# M8310F.net
KiCad netlist of a schematic drawn in EAGLE
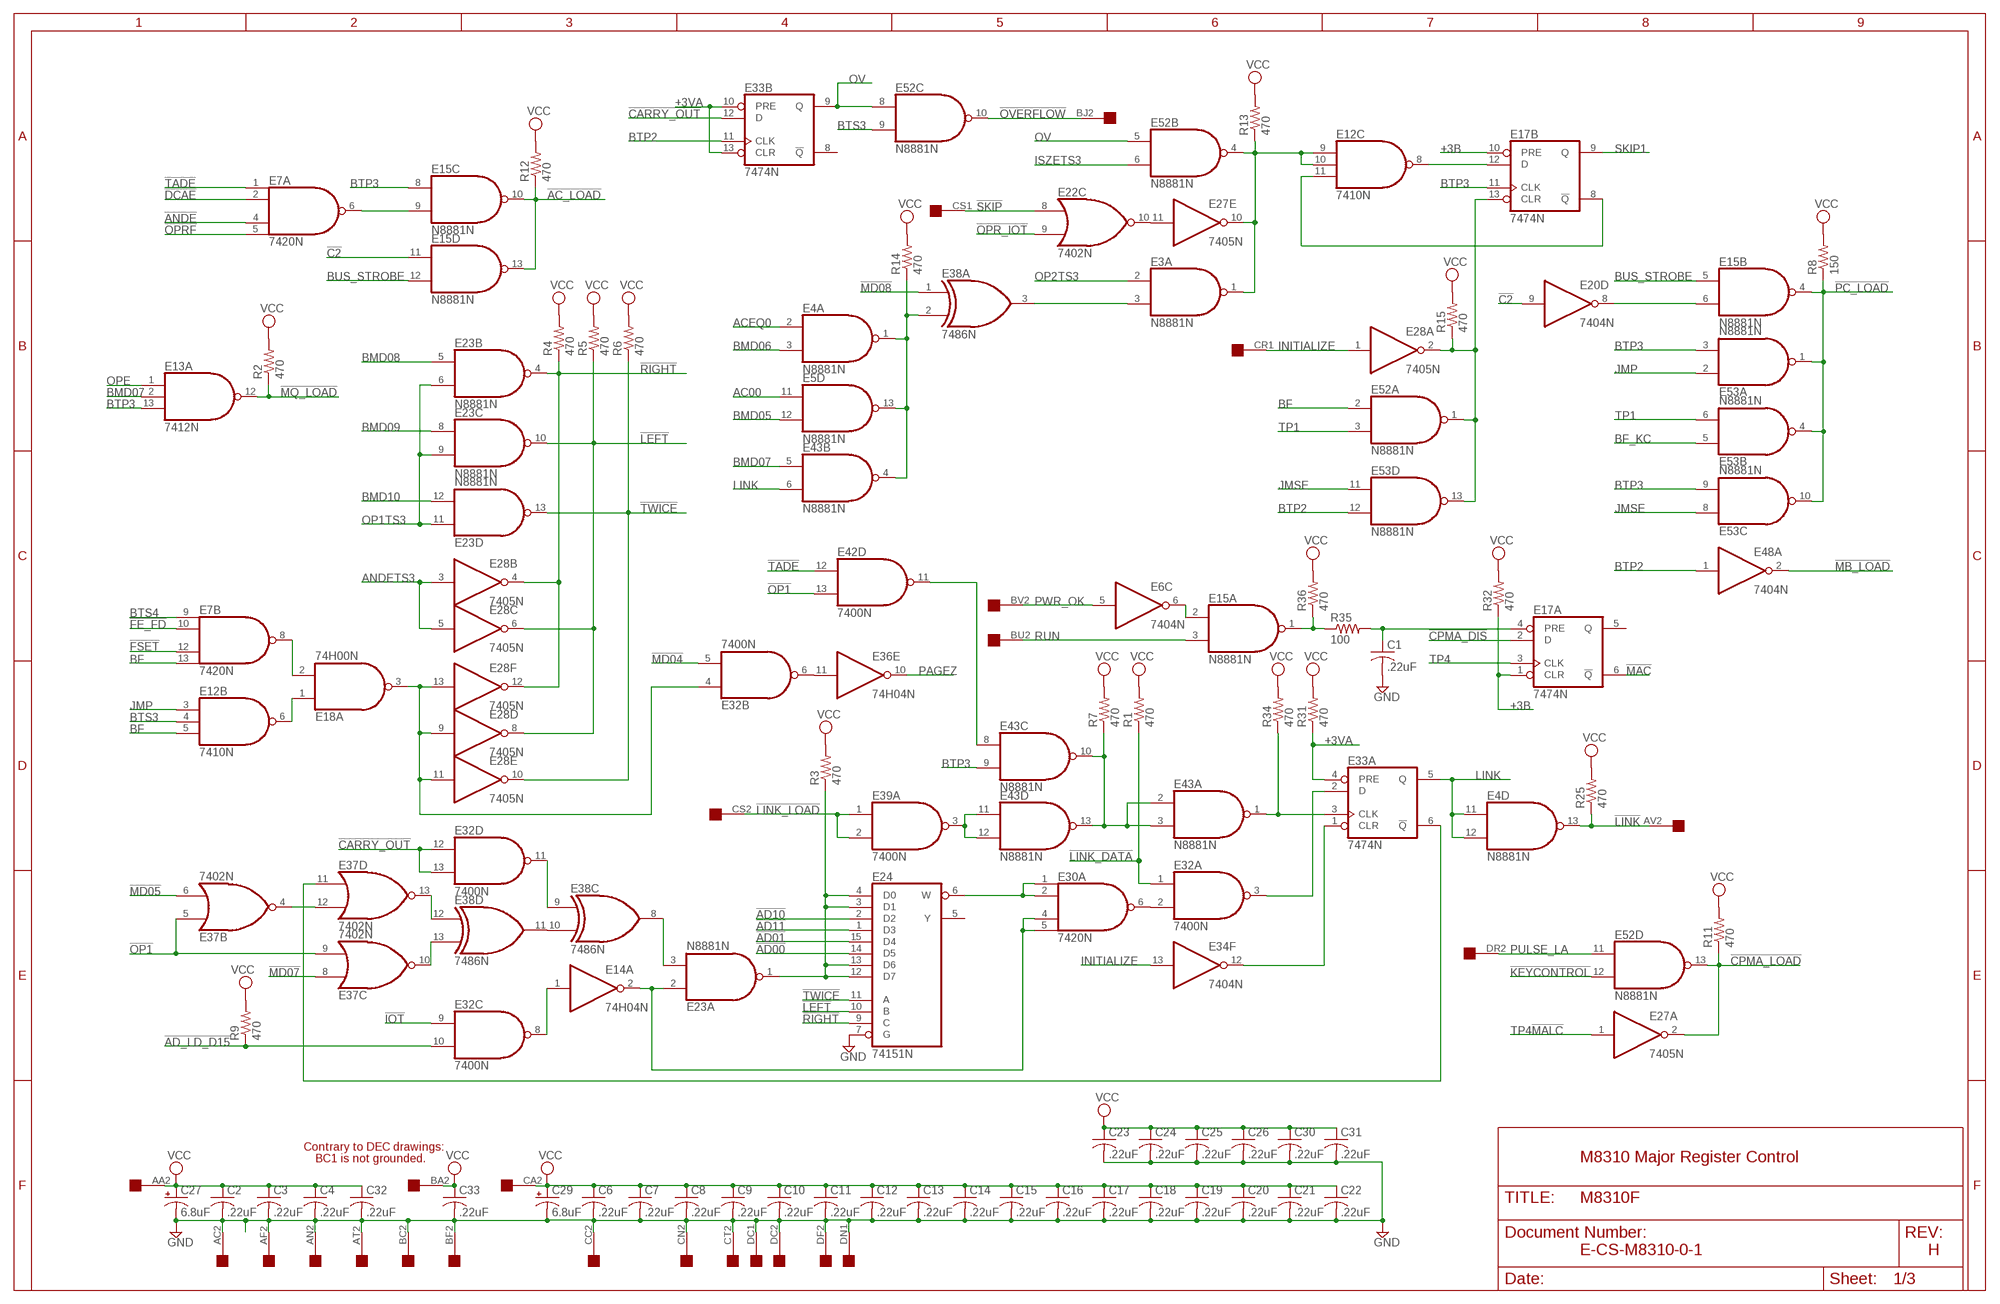
[diagram p0: schematic, sheet 1]
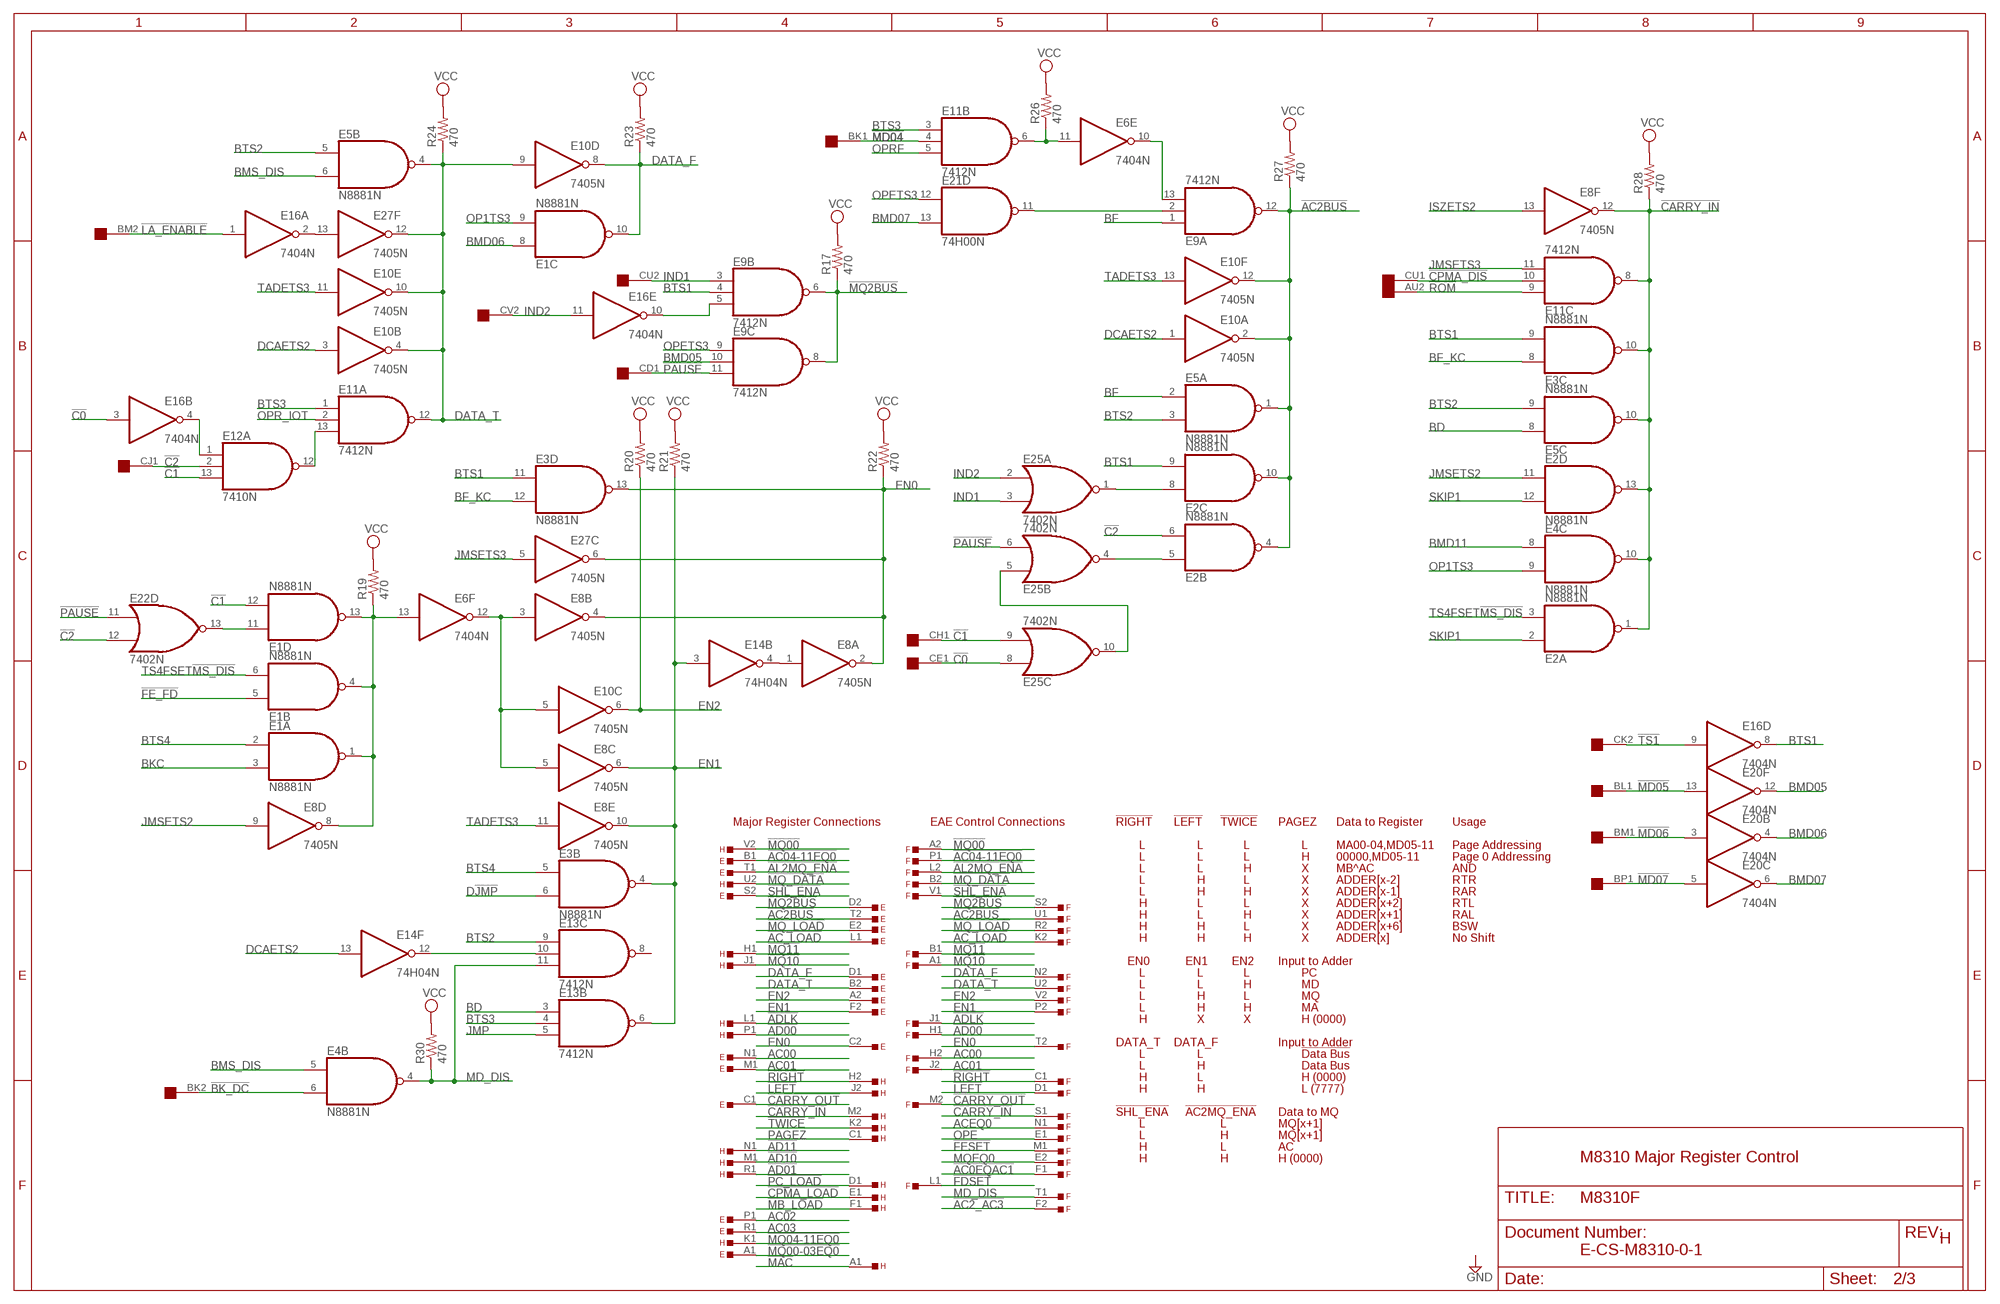
[diagram p1: schematic, sheet 2]
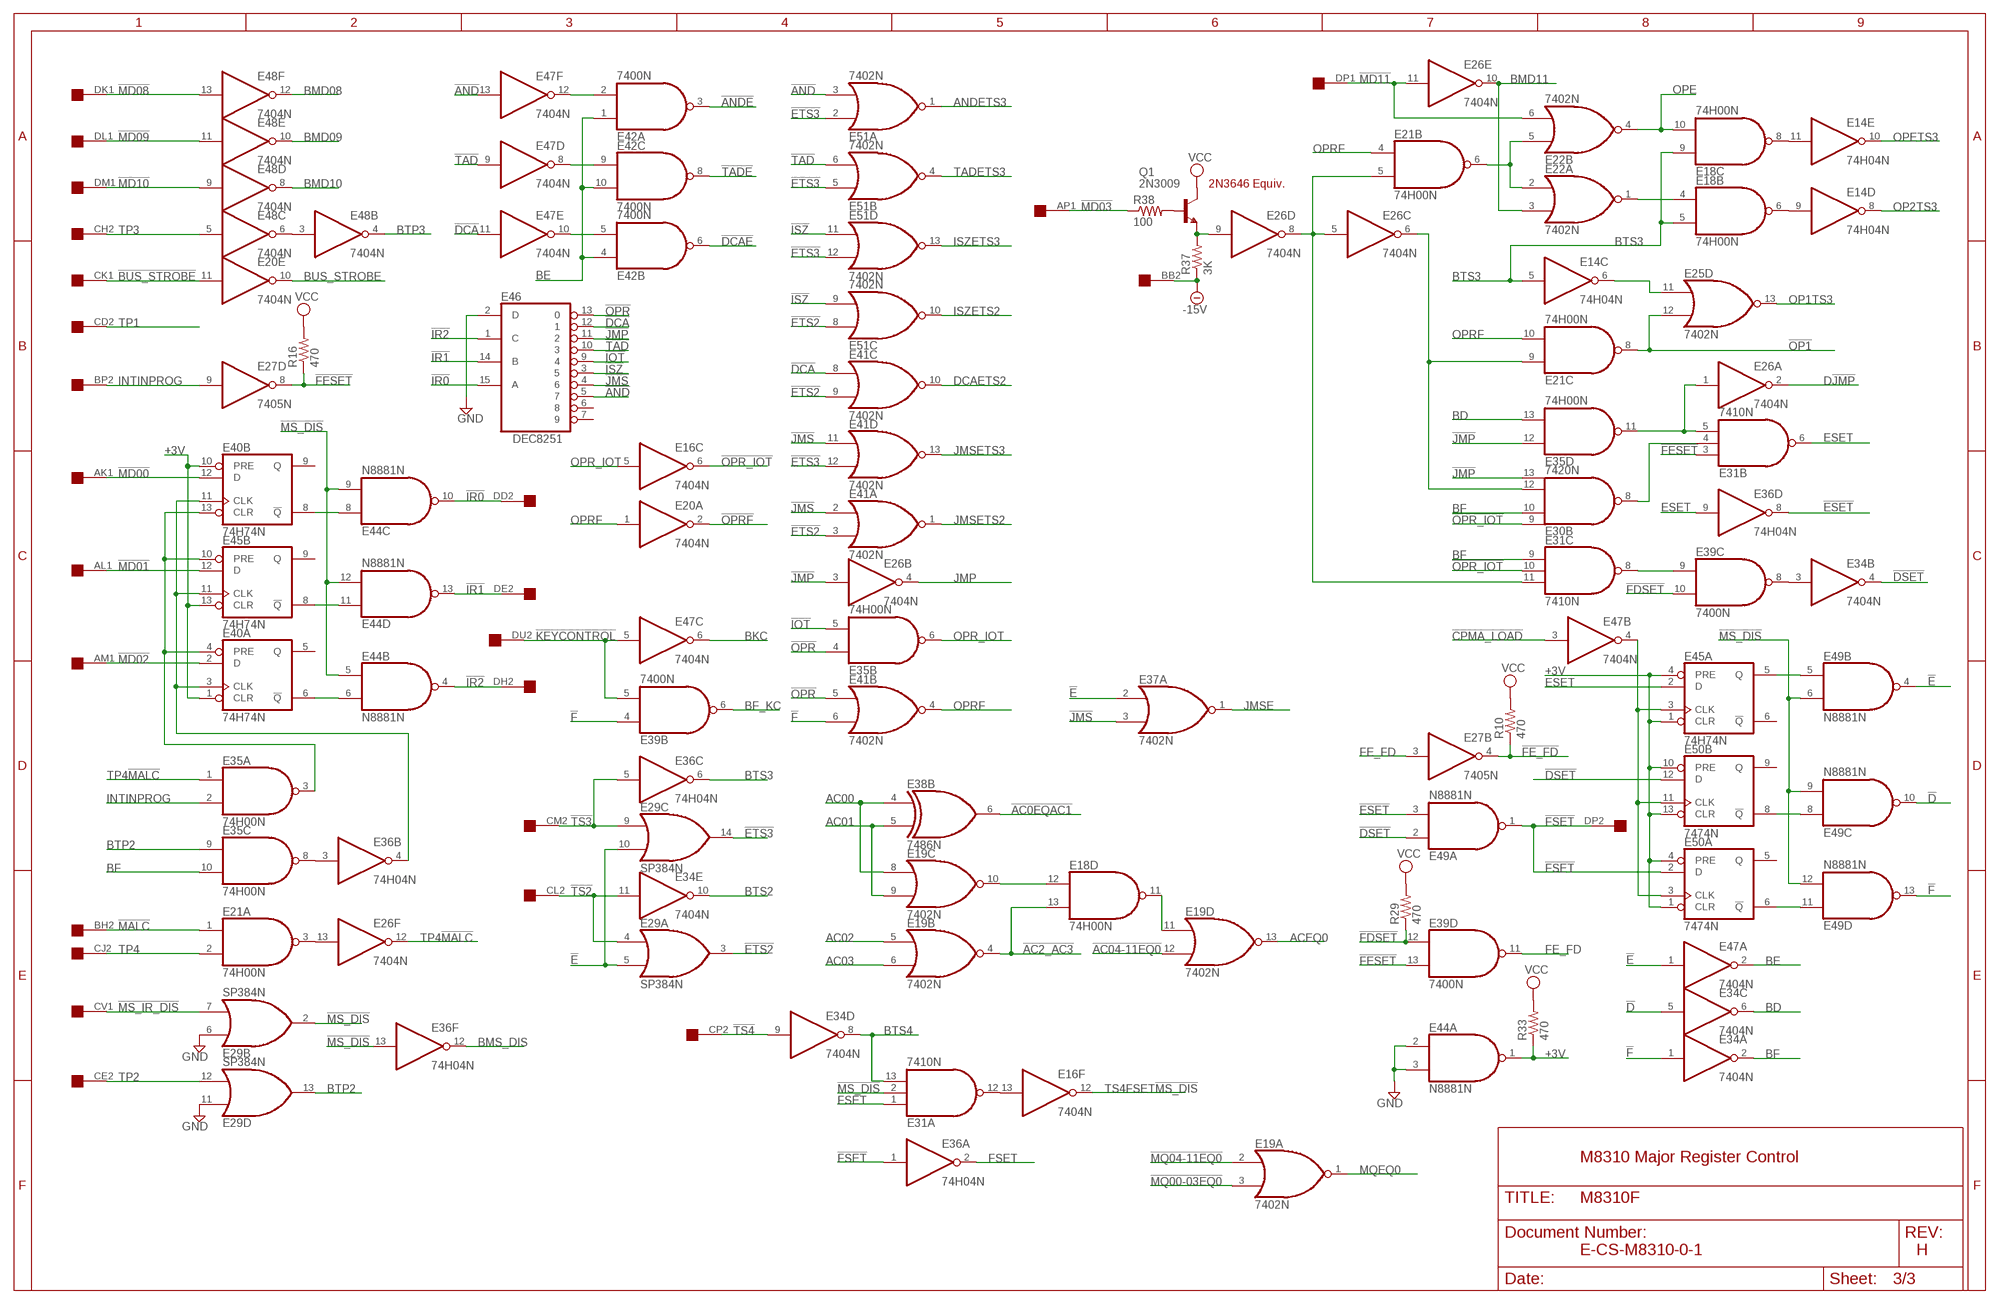
[diagram p2: schematic, sheet 3]

(export (version "E")
  (design (tool "Eeschema 10.0.6"))
  (components
    (comp (ref "C1")
      (value ".22uF")
      (footprint "eagle-import:C063-025X075")
      (libsource (lib "eagle-import") (part "C-US"))
    )
    (comp (ref "C2")
      (value ".22uF")
      (footprint "eagle-import:C063-025X075")
      (libsource (lib "eagle-import") (part "C-US"))
    )
    (comp (ref "C3")
      (value ".22uF")
      (footprint "eagle-import:C063-025X075")
      (libsource (lib "eagle-import") (part "C-US"))
    )
    (comp (ref "C4")
      (value ".22uF")
      (footprint "eagle-import:C063-025X075")
      (libsource (lib "eagle-import") (part "C-US"))
    )
    (comp (ref "C6")
      (value ".22uF")
      (footprint "eagle-import:C063-025X075")
      (libsource (lib "eagle-import") (part "C-US"))
    )
    (comp (ref "C7")
      (value ".22uF")
      (footprint "eagle-import:C063-025X075")
      (libsource (lib "eagle-import") (part "C-US"))
    )
    (comp (ref "C8")
      (value ".22uF")
      (footprint "eagle-import:C063-025X075")
      (libsource (lib "eagle-import") (part "C-US"))
    )
    (comp (ref "C9")
      (value ".22uF")
      (footprint "eagle-import:C063-025X075")
      (libsource (lib "eagle-import") (part "C-US"))
    )
    (comp (ref "C10")
      (value ".22uF")
      (footprint "eagle-import:C063-025X075")
      (libsource (lib "eagle-import") (part "C-US"))
    )
    (comp (ref "C11")
      (value ".22uF")
      (footprint "eagle-import:C063-025X075")
      (libsource (lib "eagle-import") (part "C-US"))
    )
    (comp (ref "C12")
      (value ".22uF")
      (footprint "eagle-import:C063-025X075")
      (libsource (lib "eagle-import") (part "C-US"))
    )
    (comp (ref "C13")
      (value ".22uF")
      (footprint "eagle-import:C063-025X075")
      (libsource (lib "eagle-import") (part "C-US"))
    )
    (comp (ref "C14")
      (value ".22uF")
      (footprint "eagle-import:C063-025X075")
      (libsource (lib "eagle-import") (part "C-US"))
    )
    (comp (ref "C15")
      (value ".22uF")
      (footprint "eagle-import:C063-025X075")
      (libsource (lib "eagle-import") (part "C-US"))
    )
    (comp (ref "C16")
      (value ".22uF")
      (footprint "eagle-import:C063-025X075")
      (libsource (lib "eagle-import") (part "C-US"))
    )
    (comp (ref "C17")
      (value ".22uF")
      (footprint "eagle-import:C063-025X075")
      (libsource (lib "eagle-import") (part "C-US"))
    )
    (comp (ref "C18")
      (value ".22uF")
      (footprint "eagle-import:C063-025X075")
      (libsource (lib "eagle-import") (part "C-US"))
    )
    (comp (ref "C19")
      (value ".22uF")
      (footprint "eagle-import:C063-025X075")
      (libsource (lib "eagle-import") (part "C-US"))
    )
    (comp (ref "C20")
      (value ".22uF")
      (footprint "eagle-import:C063-025X075")
      (libsource (lib "eagle-import") (part "C-US"))
    )
    (comp (ref "C21")
      (value ".22uF")
      (footprint "eagle-import:C063-025X075")
      (libsource (lib "eagle-import") (part "C-US"))
    )
    (comp (ref "C22")
      (value ".22uF")
      (footprint "eagle-import:C063-025X075")
      (libsource (lib "eagle-import") (part "C-US"))
    )
    (comp (ref "C23")
      (value ".22uF")
      (footprint "eagle-import:C063-025X075")
      (libsource (lib "eagle-import") (part "C-US"))
    )
    (comp (ref "C24")
      (value ".22uF")
      (footprint "eagle-import:C063-025X075")
      (libsource (lib "eagle-import") (part "C-US"))
    )
    (comp (ref "C25")
      (value ".22uF")
      (footprint "eagle-import:C063-025X075")
      (libsource (lib "eagle-import") (part "C-US"))
    )
    (comp (ref "C26")
      (value ".22uF")
      (footprint "eagle-import:C063-025X075")
      (libsource (lib "eagle-import") (part "C-US"))
    )
    (comp (ref "C27")
      (value "6.8uF")
      (footprint "eagle-import:E12-8")
      (libsource (lib "eagle-import") (part "CPOL-USE20-8AXIAL"))
    )
    (comp (ref "C29")
      (value "6.8uF")
      (footprint "eagle-import:E12-8")
      (libsource (lib "eagle-import") (part "CPOL-USE20-8AXIAL"))
    )
    (comp (ref "C30")
      (value ".22uF")
      (footprint "eagle-import:C063-025X075")
      (libsource (lib "eagle-import") (part "C-US"))
    )
    (comp (ref "C31")
      (value ".22uF")
      (footprint "eagle-import:C063-025X075")
      (libsource (lib "eagle-import") (part "C-US"))
    )
    (comp (ref "C32")
      (value ".22uF")
      (footprint "eagle-import:C063-025X075")
      (libsource (lib "eagle-import") (part "C-US"))
    )
    (comp (ref "C33")
      (value ".22uF")
      (footprint "eagle-import:C063-025X075")
      (libsource (lib "eagle-import") (part "C-US"))
    )
    (comp (ref "E3")
      (value "N8881N")
      (footprint "eagle-import:DIL14")
      (libsource (lib "eagle-import") (part "N8881N"))
    )
    (comp (ref "E4")
      (value "N8881N")
      (footprint "eagle-import:DIL14")
      (libsource (lib "eagle-import") (part "N8881N"))
    )
    (comp (ref "E5")
      (value "N8881N")
      (footprint "eagle-import:DIL14")
      (libsource (lib "eagle-import") (part "N8881N"))
    )
    (comp (ref "E6")
      (value "7404N")
      (footprint "eagle-import:DIL14")
      (libsource (lib "eagle-import") (part "7404N"))
    )
    (comp (ref "E7")
      (value "7420N")
      (footprint "eagle-import:DIL14")
      (libsource (lib "eagle-import") (part "7420NS"))
    )
    (comp (ref "E12")
      (value "7410N")
      (footprint "eagle-import:DIL14")
      (libsource (lib "eagle-import") (part "7410N"))
    )
    (comp (ref "E13")
      (value "7412N")
      (footprint "eagle-import:DIL14")
      (libsource (lib "eagle-import") (part "7412N"))
    )
    (comp (ref "E14")
      (value "74H04N")
      (footprint "eagle-import:DIL14")
      (libsource (lib "eagle-import") (part "7404N"))
    )
    (comp (ref "E15")
      (value "N8881N")
      (footprint "eagle-import:DIL14")
      (libsource (lib "eagle-import") (part "N8881N"))
    )
    (comp (ref "E17")
      (value "7474N")
      (footprint "eagle-import:DIL14")
      (libsource (lib "eagle-import") (part "7474NS"))
    )
    (comp (ref "E18")
      (value "74H00N")
      (footprint "eagle-import:DIL14")
      (libsource (lib "eagle-import") (part "7400N"))
    )
    (comp (ref "E20")
      (value "7404N")
      (footprint "eagle-import:DIL14")
      (libsource (lib "eagle-import") (part "7404N"))
    )
    (comp (ref "E22")
      (value "7402N")
      (footprint "eagle-import:DIL14")
      (libsource (lib "eagle-import") (part "7402N"))
    )
    (comp (ref "E23")
      (value "N8881N")
      (footprint "eagle-import:DIL14")
      (libsource (lib "eagle-import") (part "N8881N"))
    )
    (comp (ref "E24")
      (value "74151N")
      (footprint "eagle-import:DIL16")
      (libsource (lib "eagle-import") (part "74151N"))
    )
    (comp (ref "E27")
      (value "7405N")
      (footprint "eagle-import:DIL14")
      (libsource (lib "eagle-import") (part "7405N"))
    )
    (comp (ref "E28")
      (value "7405N")
      (footprint "eagle-import:DIL14")
      (libsource (lib "eagle-import") (part "7405N"))
    )
    (comp (ref "E30")
      (value "7420N")
      (footprint "eagle-import:DIL14")
      (libsource (lib "eagle-import") (part "7420NS"))
    )
    (comp (ref "E32")
      (value "7400N")
      (footprint "eagle-import:DIL14")
      (libsource (lib "eagle-import") (part "7400N"))
    )
    (comp (ref "E33")
      (value "7474N")
      (footprint "eagle-import:DIL14")
      (libsource (lib "eagle-import") (part "7474NS"))
    )
    (comp (ref "E34")
      (value "7404N")
      (footprint "eagle-import:DIL14")
      (libsource (lib "eagle-import") (part "7404N"))
    )
    (comp (ref "E36")
      (value "74H04N")
      (footprint "eagle-import:DIL14")
      (libsource (lib "eagle-import") (part "7404N"))
    )
    (comp (ref "E37")
      (value "7402N")
      (footprint "eagle-import:DIL14")
      (libsource (lib "eagle-import") (part "7402N"))
    )
    (comp (ref "E38")
      (value "7486N")
      (footprint "eagle-import:DIL14")
      (libsource (lib "eagle-import") (part "7486N"))
    )
    (comp (ref "E39")
      (value "7400N")
      (footprint "eagle-import:DIL14")
      (libsource (lib "eagle-import") (part "7400N"))
    )
    (comp (ref "E42")
      (value "7400N")
      (footprint "eagle-import:DIL14")
      (libsource (lib "eagle-import") (part "7400N"))
    )
    (comp (ref "E43")
      (value "N8881N")
      (footprint "eagle-import:DIL14")
      (libsource (lib "eagle-import") (part "N8881N"))
    )
    (comp (ref "E48")
      (value "7404N")
      (footprint "eagle-import:DIL14")
      (libsource (lib "eagle-import") (part "7404N"))
    )
    (comp (ref "E52")
      (value "N8881N")
      (footprint "eagle-import:DIL14")
      (libsource (lib "eagle-import") (part "N8881N"))
    )
    (comp (ref "E53")
      (value "N8881N")
      (footprint "eagle-import:DIL14")
      (libsource (lib "eagle-import") (part "N8881N"))
    )
    (comp (ref "R1")
      (value "470")
      (footprint "eagle-import:0207_10")
      (libsource (lib "eagle-import") (part "R-US_0207/10"))
    )
    (comp (ref "R2")
      (value "470")
      (footprint "eagle-import:0207_10")
      (libsource (lib "eagle-import") (part "R-US_0207/10"))
    )
    (comp (ref "R3")
      (value "470")
      (footprint "eagle-import:0207_10")
      (libsource (lib "eagle-import") (part "R-US_0207/10"))
    )
    (comp (ref "R4")
      (value "470")
      (footprint "eagle-import:0207_10")
      (libsource (lib "eagle-import") (part "R-US_0207/10"))
    )
    (comp (ref "R5")
      (value "470")
      (footprint "eagle-import:0207_10")
      (libsource (lib "eagle-import") (part "R-US_0207/10"))
    )
    (comp (ref "R6")
      (value "470")
      (footprint "eagle-import:0207_10")
      (libsource (lib "eagle-import") (part "R-US_0207/10"))
    )
    (comp (ref "R7")
      (value "470")
      (footprint "eagle-import:0207_10")
      (libsource (lib "eagle-import") (part "R-US_0207/10"))
    )
    (comp (ref "R8")
      (value "150")
      (footprint "eagle-import:0207_10")
      (libsource (lib "eagle-import") (part "R-US_0207/10"))
    )
    (comp (ref "R9")
      (value "470")
      (footprint "eagle-import:0207_10")
      (libsource (lib "eagle-import") (part "R-US_0207/10"))
    )
    (comp (ref "R11")
      (value "470")
      (footprint "eagle-import:0207_10")
      (libsource (lib "eagle-import") (part "R-US_0207/10"))
    )
    (comp (ref "R12")
      (value "470")
      (footprint "eagle-import:0207_10")
      (libsource (lib "eagle-import") (part "R-US_0207/10"))
    )
    (comp (ref "R13")
      (value "470")
      (footprint "eagle-import:0207_10")
      (libsource (lib "eagle-import") (part "R-US_0207/10"))
    )
    (comp (ref "R14")
      (value "470")
      (footprint "eagle-import:0207_10")
      (libsource (lib "eagle-import") (part "R-US_0207/10"))
    )
    (comp (ref "R15")
      (value "470")
      (footprint "eagle-import:0207_10")
      (libsource (lib "eagle-import") (part "R-US_0207/10"))
    )
    (comp (ref "R25")
      (value "470")
      (footprint "eagle-import:0207_10")
      (libsource (lib "eagle-import") (part "R-US_0207/10"))
    )
    (comp (ref "R31")
      (value "470")
      (footprint "eagle-import:0207_10")
      (libsource (lib "eagle-import") (part "R-US_0207/10"))
    )
    (comp (ref "R32")
      (value "470")
      (footprint "eagle-import:0207_10")
      (libsource (lib "eagle-import") (part "R-US_0207/10"))
    )
    (comp (ref "R34")
      (value "470")
      (footprint "eagle-import:0207_10")
      (libsource (lib "eagle-import") (part "R-US_0207/10"))
    )
    (comp (ref "R35")
      (value "100")
      (footprint "eagle-import:0207_10")
      (libsource (lib "eagle-import") (part "R-US_0207/10"))
    )
    (comp (ref "R36")
      (value "470")
      (footprint "eagle-import:0207_10")
      (libsource (lib "eagle-import") (part "R-US_0207/10"))
    )
    (comp (ref "U$2")
      (value "QUAD")
      (footprint "eagle-import:EDGE-CON8")
      (libsource (lib "eagle-import") (part "QUAD"))
    )
    (comp (ref "E")
      (value "EDGE-TOP")
      (footprint "eagle-import:EDGE-CON2")
      (libsource (lib "eagle-import") (part "EDGE-TOP"))
    )
    (comp (ref "E1")
      (value "N8881N")
      (footprint "eagle-import:DIL14")
      (libsource (lib "eagle-import") (part "N8881N"))
    )
    (comp (ref "E2")
      (value "N8881N")
      (footprint "eagle-import:DIL14")
      (libsource (lib "eagle-import") (part "N8881N"))
    )
    (comp (ref "E8")
      (value "7405N")
      (footprint "eagle-import:DIL14")
      (libsource (lib "eagle-import") (part "7405N"))
    )
    (comp (ref "E9")
      (value "7412N")
      (footprint "eagle-import:DIL14")
      (libsource (lib "eagle-import") (part "7412N"))
    )
    (comp (ref "E10")
      (value "7405N")
      (footprint "eagle-import:DIL14")
      (libsource (lib "eagle-import") (part "7405N"))
    )
    (comp (ref "E11")
      (value "7412N")
      (footprint "eagle-import:DIL14")
      (libsource (lib "eagle-import") (part "7412N"))
    )
    (comp (ref "E16")
      (value "7404N")
      (footprint "eagle-import:DIL14")
      (libsource (lib "eagle-import") (part "7404N"))
    )
    (comp (ref "E21")
      (value "74H00N")
      (footprint "eagle-import:DIL14")
      (libsource (lib "eagle-import") (part "7400N"))
    )
    (comp (ref "E25")
      (value "7402N")
      (footprint "eagle-import:DIL14")
      (libsource (lib "eagle-import") (part "7402N"))
    )
    (comp (ref "F")
      (value "EDGE-TOP")
      (footprint "eagle-import:EDGE-CON2")
      (libsource (lib "eagle-import") (part "EDGE-TOP"))
    )
    (comp (ref "H")
      (value "EDGE-TOP")
      (footprint "eagle-import:EDGE-CON2")
      (libsource (lib "eagle-import") (part "EDGE-TOP"))
    )
    (comp (ref "R17")
      (value "470")
      (footprint "eagle-import:0207_10")
      (libsource (lib "eagle-import") (part "R-US_0207/10"))
    )
    (comp (ref "R19")
      (value "470")
      (footprint "eagle-import:0207_10")
      (libsource (lib "eagle-import") (part "R-US_0207/10"))
    )
    (comp (ref "R20")
      (value "470")
      (footprint "eagle-import:0207_10")
      (libsource (lib "eagle-import") (part "R-US_0207/10"))
    )
    (comp (ref "R21")
      (value "470")
      (footprint "eagle-import:0207_10")
      (libsource (lib "eagle-import") (part "R-US_0207/10"))
    )
    (comp (ref "R22")
      (value "470")
      (footprint "eagle-import:0207_10")
      (libsource (lib "eagle-import") (part "R-US_0207/10"))
    )
    (comp (ref "R23")
      (value "470")
      (footprint "eagle-import:0207_10")
      (libsource (lib "eagle-import") (part "R-US_0207/10"))
    )
    (comp (ref "R24")
      (value "470")
      (footprint "eagle-import:0207_10")
      (libsource (lib "eagle-import") (part "R-US_0207/10"))
    )
    (comp (ref "R26")
      (value "470")
      (footprint "eagle-import:0207_10")
      (libsource (lib "eagle-import") (part "R-US_0207/10"))
    )
    (comp (ref "R27")
      (value "470")
      (footprint "eagle-import:0207_10")
      (libsource (lib "eagle-import") (part "R-US_0207/10"))
    )
    (comp (ref "R28")
      (value "470")
      (footprint "eagle-import:0207_10")
      (libsource (lib "eagle-import") (part "R-US_0207/10"))
    )
    (comp (ref "R30")
      (value "470")
      (footprint "eagle-import:0207_10")
      (libsource (lib "eagle-import") (part "R-US_0207/10"))
    )
    (comp (ref "E19")
      (value "7402N")
      (footprint "eagle-import:DIL14")
      (libsource (lib "eagle-import") (part "7402N"))
    )
    (comp (ref "E26")
      (value "7404N")
      (footprint "eagle-import:DIL14")
      (libsource (lib "eagle-import") (part "7404N"))
    )
    (comp (ref "E29")
      (value "SP384N")
      (footprint "eagle-import:DIL14")
      (libsource (lib "eagle-import") (part "SP384N"))
    )
    (comp (ref "E31")
      (value "7410N")
      (footprint "eagle-import:DIL14")
      (libsource (lib "eagle-import") (part "7410N"))
    )
    (comp (ref "E35")
      (value "74H00N")
      (footprint "eagle-import:DIL14")
      (libsource (lib "eagle-import") (part "7400N"))
    )
    (comp (ref "E40")
      (value "74H74N")
      (footprint "eagle-import:DIL14")
      (libsource (lib "eagle-import") (part "7474NS"))
    )
    (comp (ref "E41")
      (value "7402N")
      (footprint "eagle-import:DIL14")
      (libsource (lib "eagle-import") (part "7402N"))
    )
    (comp (ref "E44")
      (value "N8881N")
      (footprint "eagle-import:DIL14")
      (libsource (lib "eagle-import") (part "N8881N"))
    )
    (comp (ref "E45")
      (value "74H74N")
      (footprint "eagle-import:DIL14")
      (libsource (lib "eagle-import") (part "7474NS"))
    )
    (comp (ref "E46")
      (value "DEC8251")
      (footprint "eagle-import:DIL16")
      (libsource (lib "eagle-import") (part "DEC8251"))
    )
    (comp (ref "E47")
      (value "7404N")
      (footprint "eagle-import:DIL14")
      (libsource (lib "eagle-import") (part "7404N"))
    )
    (comp (ref "E49")
      (value "N8881N")
      (footprint "eagle-import:DIL14")
      (libsource (lib "eagle-import") (part "N8881N"))
    )
    (comp (ref "E50")
      (value "7474N")
      (footprint "eagle-import:DIL14")
      (libsource (lib "eagle-import") (part "7474NS"))
    )
    (comp (ref "E51")
      (value "7402N")
      (footprint "eagle-import:DIL14")
      (libsource (lib "eagle-import") (part "7402N"))
    )
    (comp (ref "Q1")
      (value "2N3009")
      (footprint "eagle-import:TO5")
      (libsource (lib "eagle-import") (part "-NPN-TO5"))
    )
    (comp (ref "R10")
      (value "470")
      (footprint "eagle-import:0207_10")
      (libsource (lib "eagle-import") (part "R-US_0207/10"))
    )
    (comp (ref "R16")
      (value "470")
      (footprint "eagle-import:0207_10")
      (libsource (lib "eagle-import") (part "R-US_0207/10"))
    )
    (comp (ref "R29")
      (value "470")
      (footprint "eagle-import:0207_10")
      (libsource (lib "eagle-import") (part "R-US_0207/10"))
    )
    (comp (ref "R33")
      (value "470")
      (footprint "eagle-import:0207_10")
      (libsource (lib "eagle-import") (part "R-US_0207/10"))
    )
    (comp (ref "R37")
      (value "3K")
      (footprint "eagle-import:0207_10")
      (libsource (lib "eagle-import") (part "R-US_0207/10"))
    )
    (comp (ref "R38")
      (value "100")
      (footprint "eagle-import:0207_10")
      (libsource (lib "eagle-import") (part "R-US_0207/10"))
    )
  )
  (nets
    (net (code "1") (name "+3B") (class "Default")
      (node (ref "E17") (pin "1") (pinfunction "CLR_1") (pintype "input"))
      (node (ref "E17") (pin "10") (pinfunction "PRE_10") (pintype "input"))
      (node (ref "R32") (pin "1") (pinfunction "1_1") (pintype "passive"))
    )
    (net (code "2") (name "+3V") (class "Default")
      (node (ref "E40") (pin "1") (pinfunction "CLR_1") (pintype "input"))
      (node (ref "E40") (pin "10") (pinfunction "PRE_10") (pintype "input"))
      (node (ref "E44") (pin "1") (pinfunction "O_1") (pintype "open_collector"))
      (node (ref "E45") (pin "1") (pinfunction "CLR_1") (pintype "input"))
      (node (ref "E45") (pin "13") (pinfunction "CLR_13") (pintype "input"))
      (node (ref "E45") (pin "4") (pinfunction "PRE_4") (pintype "input"))
      (node (ref "E50") (pin "1") (pinfunction "CLR_1") (pintype "input"))
      (node (ref "E50") (pin "10") (pinfunction "PRE_10") (pintype "input"))
      (node (ref "E50") (pin "13") (pinfunction "CLR_13") (pintype "input"))
      (node (ref "E50") (pin "4") (pinfunction "PRE_4") (pintype "input"))
      (node (ref "R33") (pin "1") (pinfunction "1_1") (pintype "passive"))
    )
    (net (code "3") (name "+3VA") (class "Default")
      (node (ref "E33") (pin "10") (pinfunction "PRE_10") (pintype "input"))
      (node (ref "E33") (pin "13") (pinfunction "CLR_13") (pintype "input"))
      (node (ref "E33") (pin "4") (pinfunction "PRE_4") (pintype "input"))
      (node (ref "R31") (pin "1") (pinfunction "1_1") (pintype "passive"))
    )
    (net (code "4") (name "-15V") (class "Default")
      (node (ref "R37") (pin "1") (pinfunction "1_1") (pintype "passive"))
      (node (ref "U$2") (pin "BB2") (pinfunction "1_BB2") (pintype "bidirectional"))
    )
    (net (code "5") (name "AC00") (class "Default")
      (node (ref "E") (pin "N1") (pinfunction "P_N1") (pintype "passive"))
      (node (ref "E19") (pin "8") (pinfunction "I0_8") (pintype "input"))
      (node (ref "E38") (pin "4") (pinfunction "I0_4") (pintype "input"))
      (node (ref "E5") (pin "11") (pinfunction "I0_11") (pintype "input"))
      (node (ref "F") (pin "H2") (pinfunction "P_H2") (pintype "passive"))
    )
    (net (code "6") (name "AC01") (class "Default")
      (node (ref "E") (pin "M1") (pinfunction "P_M1") (pintype "passive"))
      (node (ref "E19") (pin "9") (pinfunction "I1_9") (pintype "input"))
      (node (ref "E38") (pin "5") (pinfunction "I1_5") (pintype "input"))
      (node (ref "F") (pin "J2") (pinfunction "P_J2") (pintype "passive"))
    )
    (net (code "7") (name "AC02") (class "Default")
      (node (ref "E") (pin "P1") (pinfunction "P_P1") (pintype "passive"))
      (node (ref "E19") (pin "5") (pinfunction "I0_5") (pintype "input"))
    )
    (net (code "8") (name "AC03") (class "Default")
      (node (ref "E") (pin "R1") (pinfunction "P_R1") (pintype "passive"))
      (node (ref "E19") (pin "6") (pinfunction "I1_6") (pintype "input"))
    )
    (net (code "9") (name "ACEQ0") (class "Default")
      (node (ref "E19") (pin "13") (pinfunction "O_13") (pintype "output"))
      (node (ref "E4") (pin "2") (pinfunction "I0_2") (pintype "input"))
      (node (ref "F") (pin "N1") (pinfunction "P_N1") (pintype "passive"))
    )
    (net (code "10") (name "ANDETS3") (class "Default")
      (node (ref "E28") (pin "3") (pinfunction "I_3") (pintype "input"))
      (node (ref "E28") (pin "5") (pinfunction "I_5") (pintype "input"))
      (node (ref "E51") (pin "1") (pinfunction "O_1") (pintype "output"))
    )
    (net (code "11") (name "BD") (class "Default")
      (node (ref "E13") (pin "3") (pinfunction "I0_3") (pintype "input"))
      (node (ref "E34") (pin "6") (pinfunction "O_6") (pintype "output"))
      (node (ref "E35") (pin "13") (pinfunction "I1_13") (pintype "input"))
      (node (ref "E5") (pin "8") (pinfunction "I0_8") (pintype "input"))
    )
    (net (code "12") (name "BE") (class "Default")
      (node (ref "E42") (pin "1") (pinfunction "I0_1") (pintype "input"))
      (node (ref "E42") (pin "10") (pinfunction "I1_10") (pintype "input"))
      (node (ref "E42") (pin "4") (pinfunction "I0_4") (pintype "input"))
      (node (ref "E47") (pin "2") (pinfunction "O_2") (pintype "output"))
    )
    (net (code "13") (name "BF") (class "Default")
      (node (ref "E12") (pin "5") (pinfunction "I2_5") (pintype "input"))
      (node (ref "E30") (pin "10") (pinfunction "I1_10") (pintype "input"))
      (node (ref "E31") (pin "9") (pinfunction "I0_9") (pintype "input"))
      (node (ref "E34") (pin "2") (pinfunction "O_2") (pintype "output"))
      (node (ref "E35") (pin "10") (pinfunction "I1_10") (pintype "input"))
      (node (ref "E5") (pin "2") (pinfunction "I0_2") (pintype "input"))
      (node (ref "E52") (pin "2") (pinfunction "I0_2") (pintype "input"))
      (node (ref "E7") (pin "13") (pinfunction "I3_13") (pintype "input"))
      (node (ref "E9") (pin "1") (pinfunction "I0_1") (pintype "input"))
    )
    (net (code "14") (name "BF_KC") (class "Default")
      (node (ref "E3") (pin "12") (pinfunction "I1_12") (pintype "input"))
      (node (ref "E3") (pin "8") (pinfunction "I0_8") (pintype "input"))
      (node (ref "E39") (pin "6") (pinfunction "O_6") (pintype "output"))
      (node (ref "E53") (pin "5") (pinfunction "I0_5") (pintype "input"))
    )
    (net (code "15") (name "BKC") (class "Default")
      (node (ref "E1") (pin "3") (pinfunction "I1_3") (pintype "input"))
      (node (ref "E47") (pin "6") (pinfunction "O_6") (pintype "output"))
    )
    (net (code "16") (name "BMD05") (class "Default")
      (node (ref "E20") (pin "12") (pinfunction "O_12") (pintype "output"))
      (node (ref "E5") (pin "12") (pinfunction "I1_12") (pintype "input"))
      (node (ref "E9") (pin "10") (pinfunction "I1_10") (pintype "input"))
    )
    (net (code "17") (name "BMD06") (class "Default")
      (node (ref "E1") (pin "8") (pinfunction "I0_8") (pintype "input"))
      (node (ref "E20") (pin "4") (pinfunction "O_4") (pintype "output"))
      (node (ref "E4") (pin "3") (pinfunction "I1_3") (pintype "input"))
    )
    (net (code "18") (name "BMD07") (class "Default")
      (node (ref "E13") (pin "2") (pinfunction "I1_2") (pintype "input"))
      (node (ref "E20") (pin "6") (pinfunction "O_6") (pintype "output"))
      (node (ref "E21") (pin "13") (pinfunction "I1_13") (pintype "input"))
      (node (ref "E43") (pin "5") (pinfunction "I0_5") (pintype "input"))
    )
    (net (code "19") (name "BMD08") (class "Default")
      (node (ref "E23") (pin "5") (pinfunction "I0_5") (pintype "input"))
      (node (ref "E48") (pin "12") (pinfunction "O_12") (pintype "output"))
    )
    (net (code "20") (name "BMD09") (class "Default")
      (node (ref "E23") (pin "8") (pinfunction "I0_8") (pintype "input"))
      (node (ref "E48") (pin "10") (pinfunction "O_10") (pintype "output"))
    )
    (net (code "21") (name "BMD10") (class "Default")
      (node (ref "E23") (pin "12") (pinfunction "I1_12") (pintype "input"))
      (node (ref "E48") (pin "8") (pinfunction "O_8") (pintype "output"))
    )
    (net (code "22") (name "BMD11") (class "Default")
      (node (ref "E22") (pin "3") (pinfunction "I1_3") (pintype "input"))
      (node (ref "E26") (pin "10") (pinfunction "O_10") (pintype "output"))
      (node (ref "E4") (pin "8") (pinfunction "I0_8") (pintype "input"))
    )
    (net (code "23") (name "BMS_DIS") (class "Default")
      (node (ref "E36") (pin "12") (pinfunction "O_12") (pintype "output"))
      (node (ref "E4") (pin "5") (pinfunction "I0_5") (pintype "input"))
      (node (ref "E5") (pin "6") (pinfunction "I1_6") (pintype "input"))
    )
    (net (code "24") (name "BTP2") (class "Default")
      (node (ref "E29") (pin "13") (pinfunction "O_13") (pintype "output"))
      (node (ref "E33") (pin "11") (pinfunction "CLK_11") (pintype "input"))
      (node (ref "E35") (pin "9") (pinfunction "I0_9") (pintype "input"))
      (node (ref "E48") (pin "1") (pinfunction "I_1") (pintype "input"))
      (node (ref "E53") (pin "12") (pinfunction "I1_12") (pintype "input"))
    )
    (net (code "25") (name "BTP3") (class "Default")
      (node (ref "E13") (pin "13") (pinfunction "I2_13") (pintype "input"))
      (node (ref "E15") (pin "8") (pinfunction "I0_8") (pintype "input"))
      (node (ref "E17") (pin "11") (pinfunction "CLK_11") (pintype "input"))
      (node (ref "E43") (pin "9") (pinfunction "I1_9") (pintype "input"))
      (node (ref "E48") (pin "4") (pinfunction "O_4") (pintype "output"))
      (node (ref "E53") (pin "3") (pinfunction "I1_3") (pintype "input"))
      (node (ref "E53") (pin "9") (pinfunction "I1_9") (pintype "input"))
    )
    (net (code "26") (name "BTS1") (class "Default")
      (node (ref "E16") (pin "8") (pinfunction "O_8") (pintype "output"))
      (node (ref "E2") (pin "9") (pinfunction "I1_9") (pintype "input"))
      (node (ref "E3") (pin "11") (pinfunction "I0_11") (pintype "input"))
      (node (ref "E3") (pin "9") (pinfunction "I1_9") (pintype "input"))
      (node (ref "E9") (pin "4") (pinfunction "I1_4") (pintype "input"))
    )
    (net (code "27") (name "BTS2") (class "Default")
      (node (ref "E13") (pin "9") (pinfunction "I0_9") (pintype "input"))
      (node (ref "E34") (pin "10") (pinfunction "O_10") (pintype "output"))
      (node (ref "E5") (pin "3") (pinfunction "I1_3") (pintype "input"))
      (node (ref "E5") (pin "5") (pinfunction "I0_5") (pintype "input"))
      (node (ref "E5") (pin "9") (pinfunction "I1_9") (pintype "input"))
    )
    (net (code "28") (name "BTS3") (class "Default")
      (node (ref "E11") (pin "1") (pinfunction "I0_1") (pintype "input"))
      (node (ref "E11") (pin "3") (pinfunction "I0_3") (pintype "input"))
      (node (ref "E12") (pin "4") (pinfunction "I1_4") (pintype "input"))
      (node (ref "E13") (pin "4") (pinfunction "I1_4") (pintype "input"))
      (node (ref "E14") (pin "5") (pinfunction "I_5") (pintype "input"))
      (node (ref "E18") (pin "5") (pinfunction "I1_5") (pintype "input"))
      (node (ref "E18") (pin "9") (pinfunction "I0_9") (pintype "input"))
      (node (ref "E36") (pin "6") (pinfunction "O_6") (pintype "output"))
      (node (ref "E52") (pin "9") (pinfunction "I1_9") (pintype "input"))
    )
    (net (code "29") (name "BTS4") (class "Default")
      (node (ref "E1") (pin "2") (pinfunction "I0_2") (pintype "input"))
      (node (ref "E3") (pin "5") (pinfunction "I0_5") (pintype "input"))
      (node (ref "E31") (pin "13") (pinfunction "I2_13") (pintype "input"))
      (node (ref "E34") (pin "8") (pinfunction "O_8") (pintype "output"))
      (node (ref "E7") (pin "9") (pinfunction "I0_9") (pintype "input"))
    )
    (net (code "30") (name "BUS_STROBE") (class "Default")
      (node (ref "E15") (pin "12") (pinfunction "I1_12") (pintype "input"))
      (node (ref "E15") (pin "5") (pinfunction "I0_5") (pintype "input"))
      (node (ref "E20") (pin "10") (pinfunction "O_10") (pintype "output"))
    )
    (net (code "31") (name "DATA_F") (class "Default")
      (node (ref "E") (pin "D1") (pinfunction "P_D1") (pintype "passive"))
      (node (ref "E1") (pin "10") (pinfunction "O_10") (pintype "open_collector"))
      (node (ref "E10") (pin "8") (pinfunction "O_8") (pintype "open_collector"))
      (node (ref "F") (pin "N2") (pinfunction "P_N2") (pintype "passive"))
      (node (ref "R23") (pin "1") (pinfunction "1_1") (pintype "passive"))
    )
    (net (code "32") (name "DATA_T") (class "Default")
      (node (ref "E") (pin "B2") (pinfunction "P_B2") (pintype "passive"))
      (node (ref "E10") (pin "10") (pinfunction "O_10") (pintype "open_collector"))
      (node (ref "E10") (pin "4") (pinfunction "O_4") (pintype "open_collector"))
      (node (ref "E10") (pin "9") (pinfunction "I_9") (pintype "input"))
      (node (ref "E11") (pin "12") (pinfunction "O_12") (pintype "open_collector"))
      (node (ref "E27") (pin "12") (pinfunction "O_12") (pintype "open_collector"))
      (node (ref "E5") (pin "4") (pinfunction "O_4") (pintype "open_collector"))
      (node (ref "F") (pin "U2") (pinfunction "P_U2") (pintype "passive"))
      (node (ref "R24") (pin "1") (pinfunction "1_1") (pintype "passive"))
    )
    (net (code "33") (name "DCAETS2") (class "Default")
      (node (ref "E10") (pin "1") (pinfunction "I_1") (pintype "input"))
      (node (ref "E10") (pin "3") (pinfunction "I_3") (pintype "input"))
      (node (ref "E14") (pin "13") (pinfunction "I_13") (pintype "input"))
      (node (ref "E41") (pin "10") (pinfunction "O_10") (pintype "output"))
    )
    (net (code "34") (name "D~{JMP}") (class "Default")
      (node (ref "E26") (pin "2") (pinfunction "O_2") (pintype "output"))
      (node (ref "E3") (pin "6") (pinfunction "I1_6") (pintype "input"))
    )
    (net (code "35") (name "EN0") (class "Default")
      (node (ref "E") (pin "C2") (pinfunction "P_C2") (pintype "passive"))
      (node (ref "E27") (pin "6") (pinfunction "O_6") (pintype "open_collector"))
      (node (ref "E3") (pin "13") (pinfunction "O_13") (pintype "open_collector"))
      (node (ref "E8") (pin "2") (pinfunction "O_2") (pintype "open_collector"))
      (node (ref "E8") (pin "4") (pinfunction "O_4") (pintype "open_collector"))
      (node (ref "F") (pin "T2") (pinfunction "P_T2") (pintype "passive"))
      (node (ref "R22") (pin "1") (pinfunction "1_1") (pintype "passive"))
    )
    (net (code "36") (name "EN1") (class "Default")
      (node (ref "E") (pin "F2") (pinfunction "P_F2") (pintype "passive"))
      (node (ref "E13") (pin "6") (pinfunction "O_6") (pintype "open_collector"))
      (node (ref "E14") (pin "3") (pinfunction "I_3") (pintype "input"))
      (node (ref "E3") (pin "4") (pinfunction "O_4") (pintype "open_collector"))
      (node (ref "E8") (pin "10") (pinfunction "O_10") (pintype "open_collector"))
      (node (ref "E8") (pin "6") (pinfunction "O_6") (pintype "open_collector"))
      (node (ref "F") (pin "P2") (pinfunction "P_P2") (pintype "passive"))
      (node (ref "R21") (pin "1") (pinfunction "1_1") (pintype "passive"))
    )
    (net (code "37") (name "EN2") (class "Default")
      (node (ref "E") (pin "A2") (pinfunction "P_A2") (pintype "passive"))
      (node (ref "E10") (pin "6") (pinfunction "O_6") (pintype "open_collector"))
      (node (ref "F") (pin "V2") (pinfunction "P_V2") (pintype "passive"))
      (node (ref "R20") (pin "1") (pinfunction "1_1") (pintype "passive"))
    )
    (net (code "38") (name "ESET") (class "Default")
      (node (ref "E31") (pin "6") (pinfunction "O_6") (pintype "output"))
      (node (ref "E36") (pin "9") (pinfunction "I_9") (pintype "input"))
      (node (ref "E45") (pin "2") (pinfunction "D_2") (pintype "input"))
    )
    (net (code "39") (name "FE_FD") (class "Default")
      (node (ref "E27") (pin "3") (pinfunction "I_3") (pintype "input"))
      (node (ref "E39") (pin "11") (pinfunction "O_11") (pintype "output"))
    )
    (net (code "40") (name "FSET") (class "Default")
      (node (ref "E31") (pin "1") (pinfunction "I0_1") (pintype "input"))
      (node (ref "E36") (pin "2") (pinfunction "O_2") (pintype "output"))
    )
    (net (code "41") (name "GND") (class "Default")
      (node (ref "C1") (pin "2") (pinfunction "2_2") (pintype "passive"))
      (node (ref "C10") (pin "2") (pinfunction "2_2") (pintype "passive"))
      (node (ref "C11") (pin "2") (pinfunction "2_2") (pintype "passive"))
      (node (ref "C12") (pin "2") (pinfunction "2_2") (pintype "passive"))
      (node (ref "C13") (pin "2") (pinfunction "2_2") (pintype "passive"))
      (node (ref "C14") (pin "2") (pinfunction "2_2") (pintype "passive"))
      (node (ref "C15") (pin "2") (pinfunction "2_2") (pintype "passive"))
      (node (ref "C16") (pin "2") (pinfunction "2_2") (pintype "passive"))
      (node (ref "C17") (pin "2") (pinfunction "2_2") (pintype "passive"))
      (node (ref "C18") (pin "2") (pinfunction "2_2") (pintype "passive"))
      (node (ref "C19") (pin "2") (pinfunction "2_2") (pintype "passive"))
      (node (ref "C2") (pin "2") (pinfunction "2_2") (pintype "passive"))
      (node (ref "C20") (pin "2") (pinfunction "2_2") (pintype "passive"))
      (node (ref "C21") (pin "2") (pinfunction "2_2") (pintype "passive"))
      (node (ref "C22") (pin "2") (pinfunction "2_2") (pintype "passive"))
      (node (ref "C23") (pin "2") (pinfunction "2_2") (pintype "passive"))
      (node (ref "C24") (pin "2") (pinfunction "2_2") (pintype "passive"))
      (node (ref "C25") (pin "2") (pinfunction "2_2") (pintype "passive"))
      (node (ref "C26") (pin "2") (pinfunction "2_2") (pintype "passive"))
      (node (ref "C27") (pin "-") (pinfunction "-_-") (pintype "passive"))
      (node (ref "C29") (pin "-") (pinfunction "-_-") (pintype "passive"))
      (node (ref "C3") (pin "2") (pinfunction "2_2") (pintype "passive"))
      (node (ref "C30") (pin "2") (pinfunction "2_2") (pintype "passive"))
      (node (ref "C31") (pin "2") (pinfunction "2_2") (pintype "passive"))
      (node (ref "C32") (pin "2") (pinfunction "2_2") (pintype "passive"))
      (node (ref "C33") (pin "2") (pinfunction "2_2") (pintype "passive"))
      (node (ref "C4") (pin "2") (pinfunction "2_2") (pintype "passive"))
      (node (ref "C6") (pin "2") (pinfunction "2_2") (pintype "passive"))
      (node (ref "C7") (pin "2") (pinfunction "2_2") (pintype "passive"))
      (node (ref "C8") (pin "2") (pinfunction "2_2") (pintype "passive"))
      (node (ref "C9") (pin "2") (pinfunction "2_2") (pintype "passive"))
      (node (ref "E24") (pin "7") (pinfunction "G_7") (pintype "input"))
      (node (ref "E29") (pin "11") (pinfunction "I0_11") (pintype "input"))
      (node (ref "E29") (pin "6") (pinfunction "I0_6") (pintype "input"))
      (node (ref "E44") (pin "2") (pinfunction "I0_2") (pintype "input"))
      (node (ref "E44") (pin "3") (pinfunction "I1_3") (pintype "input"))
      (node (ref "E46") (pin "2") (pinfunction "D_2") (pintype "input"))
      (node (ref "U$2") (pin "AC2") (pinfunction "1_AC2") (pintype "bidirectional"))
      (node (ref "U$2") (pin "AF2") (pinfunction "1_AF2") (pintype "bidirectional"))
      (node (ref "U$2") (pin "AN2") (pinfunction "1_AN2") (pintype "bidirectional"))
      (node (ref "U$2") (pin "AT2") (pinfunction "1_AT2") (pintype "bidirectional"))
      (node (ref "U$2") (pin "BC2") (pinfunction "1_BC2") (pintype "bidirectional"))
      (node (ref "U$2") (pin "BF2") (pinfunction "1_BF2") (pintype "bidirectional"))
      (node (ref "U$2") (pin "CC2") (pinfunction "1_CC2") (pintype "bidirectional"))
      (node (ref "U$2") (pin "CN2") (pinfunction "1_CN2") (pintype "bidirectional"))
      (node (ref "U$2") (pin "CT2") (pinfunction "1_CT2") (pintype "bidirectional"))
      (node (ref "U$2") (pin "DC1") (pinfunction "1_DC1") (pintype "bidirectional"))
      (node (ref "U$2") (pin "DC2") (pinfunction "1_DC2") (pintype "bidirectional"))
      (node (ref "U$2") (pin "DF2") (pinfunction "1_DF2") (pintype "bidirectional"))
      (node (ref "U$2") (pin "DN1") (pinfunction "1_DN1") (pintype "bidirectional"))
    )
    (net (code "42") (name "IND1") (class "Default")
      (node (ref "E25") (pin "3") (pinfunction "I1_3") (pintype "input"))
      (node (ref "E9") (pin "3") (pinfunction "I0_3") (pintype "input"))
      (node (ref "U$2") (pin "CU2") (pinfunction "1_CU2") (pintype "bidirectional"))
    )
    (net (code "43") (name "IND2") (class "Default")
      (node (ref "E16") (pin "11") (pinfunction "I_11") (pintype "input"))
      (node (ref "E25") (pin "2") (pinfunction "I0_2") (pintype "input"))
      (node (ref "U$2") (pin "CV2") (pinfunction "1_CV2") (pintype "bidirectional"))
    )
    (net (code "44") (name "INITIALIZE") (class "Default")
      (node (ref "E28") (pin "1") (pinfunction "I_1") (pintype "input"))
      (node (ref "E34") (pin "13") (pinfunction "I_13") (pintype "input"))
      (node (ref "U$2") (pin "CR1") (pinfunction "1_CR1") (pintype "bidirectional"))
    )
    (net (code "45") (name "INTINPROG") (class "Default")
      (node (ref "E27") (pin "9") (pinfunction "I_9") (pintype "input"))
      (node (ref "E35") (pin "2") (pinfunction "I1_2") (pintype "input"))
      (node (ref "U$2") (pin "BP2") (pinfunction "1_BP2") (pintype "bidirectional"))
    )
    (net (code "46") (name "ISZETS2") (class "Default")
      (node (ref "E51") (pin "10") (pinfunction "O_10") (pintype "output"))
      (node (ref "E8") (pin "13") (pinfunction "I_13") (pintype "input"))
    )
    (net (code "47") (name "ISZETS3") (class "Default")
      (node (ref "E51") (pin "13") (pinfunction "O_13") (pintype "output"))
      (node (ref "E52") (pin "6") (pinfunction "I1_6") (pintype "input"))
    )
    (net (code "48") (name "JMP") (class "Default")
      (node (ref "E12") (pin "3") (pinfunction "I0_3") (pintype "input"))
      (node (ref "E13") (pin "5") (pinfunction "I2_5") (pintype "input"))
      (node (ref "E26") (pin "4") (pinfunction "O_4") (pintype "output"))
      (node (ref "E53") (pin "2") (pinfunction "I0_2") (pintype "input"))
    )
    (net (code "49") (name "JMSE") (class "Default")
      (node (ref "E37") (pin "1") (pinfunction "O_1") (pintype "output"))
      (node (ref "E53") (pin "11") (pinfunction "I0_11") (pintype "input"))
      (node (ref "E53") (pin "8") (pinfunction "I0_8") (pintype "input"))
    )
    (net (code "50") (name "JMSETS2") (class "Default")
      (node (ref "E2") (pin "11") (pinfunction "I0_11") (pintype "input"))
      (node (ref "E41") (pin "1") (pinfunction "O_1") (pintype "output"))
      (node (ref "E8") (pin "9") (pinfunction "I_9") (pintype "input"))
    )
    (net (code "51") (name "JMSETS3") (class "Default")
      (node (ref "E11") (pin "11") (pinfunction "I2_11") (pintype "input"))
      (node (ref "E27") (pin "5") (pinfunction "I_5") (pintype "input"))
      (node (ref "E41") (pin "13") (pinfunction "O_13") (pintype "output"))
    )
    (net (code "52") (name "LINK") (class "Default")
      (node (ref "E33") (pin "5") (pinfunction "Q_5") (pintype "output"))
      (node (ref "E4") (pin "11") (pinfunction "I0_11") (pintype "input"))
      (node (ref "E4") (pin "12") (pinfunction "I1_12") (pintype "input"))
      (node (ref "E43") (pin "6") (pinfunction "I1_6") (pintype "input"))
    )
    (net (code "53") (name "MD_DIS") (class "Default")
      (node (ref "E13") (pin "11") (pinfunction "I2_11") (pintype "input"))
      (node (ref "E4") (pin "4") (pinfunction "O_4") (pintype "open_collector"))
      (node (ref "F") (pin "T1") (pinfunction "P_T1") (pintype "passive"))
      (node (ref "R30") (pin "1") (pinfunction "1_1") (pintype "passive"))
    )
    (net (code "54") (name "MQEQ0") (class "Default")
      (node (ref "E19") (pin "1") (pinfunction "O_1") (pintype "output"))
      (node (ref "F") (pin "E2") (pinfunction "P_E2") (pintype "passive"))
    )
    (net (code "55") (name "Net-(E1A-O)") (class "Default")
      (node (ref "E1") (pin "1") (pinfunction "O_1") (pintype "open_collector"))
      (node (ref "E1") (pin "13") (pinfunction "O_13") (pintype "open_collector"))
      (node (ref "E1") (pin "4") (pinfunction "O_4") (pintype "open_collector"))
      (node (ref "E6") (pin "13") (pinfunction "I_13") (pintype "input"))
      (node (ref "E8") (pin "8") (pinfunction "O_8") (pintype "open_collector"))
      (node (ref "R19") (pin "1") (pinfunction "1_1") (pintype "passive"))
    )
    (net (code "56") (name "Net-(E1D-I0)") (class "Default")
      (node (ref "E1") (pin "11") (pinfunction "I0_11") (pintype "input"))
      (node (ref "E22") (pin "13") (pinfunction "O_13") (pintype "output"))
    )
    (net (code "57") (name "Net-(E6E-O)") (class "Default")
      (node (ref "E6") (pin "10") (pinfunction "O_10") (pintype "output"))
      (node (ref "E9") (pin "13") (pinfunction "I2_13") (pintype "input"))
    )
    (net (code "58") (name "Net-(E10C-I)") (class "Default")
      (node (ref "E10") (pin "5") (pinfunction "I_5") (pintype "input"))
      (node (ref "E6") (pin "12") (pinfunction "O_12") (pintype "output"))
      (node (ref "E8") (pin "3") (pinfunction "I_3") (pintype "input"))
      (node (ref "E8") (pin "5") (pinfunction "I_5") (pintype "input"))
    )
    (net (code "59") (name "Net-(E11A-I2)") (class "Default")
      (node (ref "E11") (pin "13") (pinfunction "I2_13") (pintype "input"))
      (node (ref "E12") (pin "12") (pinfunction "O_12") (pintype "output"))
    )
    (net (code "60") (name "Net-(E11B-O)") (class "Default")
      (node (ref "E11") (pin "6") (pinfunction "O_6") (pintype "open_collector"))
      (node (ref "E6") (pin "11") (pinfunction "I_11") (pintype "input"))
      (node (ref "R26") (pin "1") (pinfunction "1_1") (pintype "passive"))
    )
    (net (code "61") (name "Net-(E12A-I0)") (class "Default")
      (node (ref "E12") (pin "1") (pinfunction "I0_1") (pintype "input"))
      (node (ref "E16") (pin "4") (pinfunction "O_4") (pintype "output"))
    )
    (net (code "62") (name "Net-(E12B-O)") (class "Default")
      (node (ref "E12") (pin "6") (pinfunction "O_6") (pintype "output"))
      (node (ref "E18") (pin "1") (pinfunction "I0_1") (pintype "input"))
    )
    (net (code "63") (name "Net-(E12C-I0)") (class "Default")
      (node (ref "E12") (pin "10") (pinfunction "I1_10") (pintype "input"))
      (node (ref "E12") (pin "9") (pinfunction "I0_9") (pintype "input"))
      (node (ref "E27") (pin "10") (pinfunction "O_10") (pintype "open_collector"))
      (node (ref "E3") (pin "1") (pinfunction "O_1") (pintype "open_collector"))
      (node (ref "E52") (pin "4") (pinfunction "O_4") (pintype "open_collector"))
      (node (ref "R13") (pin "1") (pinfunction "1_1") (pintype "passive"))
    )
    (net (code "64") (name "Net-(E12C-I2)") (class "Default")
      (node (ref "E12") (pin "11") (pinfunction "I2_11") (pintype "input"))
      (node (ref "E17") (pin "8") (pinfunction "~{Q}_8") (pintype "output"))
    )
    (net (code "65") (name "Net-(E12C-O)") (class "Default")
      (node (ref "E12") (pin "8") (pinfunction "O_8") (pintype "output"))
      (node (ref "E17") (pin "12") (pinfunction "D_12") (pintype "input"))
    )
    (net (code "66") (name "Net-(E13C-I1)") (class "Default")
      (node (ref "E13") (pin "10") (pinfunction "I1_10") (pintype "input"))
      (node (ref "E14") (pin "12") (pinfunction "O_12") (pintype "output"))
    )
    (net (code "67") (name "Net-(E14A-I)") (class "Default")
      (node (ref "E14") (pin "1") (pinfunction "I_1") (pintype "input"))
      (node (ref "E32") (pin "8") (pinfunction "O_8") (pintype "output"))
    )
    (net (code "68") (name "Net-(E14A-O)") (class "Default")
      (node (ref "E14") (pin "2") (pinfunction "O_2") (pintype "output"))
      (node (ref "E23") (pin "2") (pinfunction "I0_2") (pintype "input"))
      (node (ref "E30") (pin "4") (pinfunction "I2_4") (pintype "input"))
      (node (ref "E30") (pin "5") (pinfunction "I3_5") (pintype "input"))
    )
    (net (code "69") (name "Net-(E14B-O)") (class "Default")
      (node (ref "E14") (pin "4") (pinfunction "O_4") (pintype "output"))
      (node (ref "E8") (pin "1") (pinfunction "I_1") (pintype "input"))
    )
    (net (code "70") (name "Net-(E14C-O)") (class "Default")
      (node (ref "E14") (pin "6") (pinfunction "O_6") (pintype "output"))
      (node (ref "E25") (pin "11") (pinfunction "I0_11") (pintype "input"))
    )
    (net (code "71") (name "Net-(E14D-I)") (class "Default")
      (node (ref "E14") (pin "9") (pinfunction "I_9") (pintype "input"))
      (node (ref "E18") (pin "6") (pinfunction "O_6") (pintype "output"))
    )
    (net (code "72") (name "Net-(E14E-I)") (class "Default")
      (node (ref "E14") (pin "11") (pinfunction "I_11") (pintype "input"))
      (node (ref "E18") (pin "8") (pinfunction "O_8") (pintype "output"))
    )
    (net (code "73") (name "Net-(E15A-I0)") (class "Default")
      (node (ref "E15") (pin "2") (pinfunction "I0_2") (pintype "input"))
      (node (ref "E6") (pin "6") (pinfunction "O_6") (pintype "output"))
    )
    (net (code "74") (name "Net-(E15A-O)") (class "Default")
      (node (ref "E15") (pin "1") (pinfunction "O_1") (pintype "open_collector"))
      (node (ref "R35") (pin "1") (pinfunction "1_1") (pintype "passive"))
      (node (ref "R36") (pin "1") (pinfunction "1_1") (pintype "passive"))
    )
    (net (code "75") (name "Net-(E15B-I1)") (class "Default")
      (node (ref "E15") (pin "6") (pinfunction "I1_6") (pintype "input"))
      (node (ref "E20") (pin "8") (pinfunction "O_8") (pintype "output"))
    )
    (net (code "76") (name "Net-(E15C-I1)") (class "Default")
      (node (ref "E15") (pin "9") (pinfunction "I1_9") (pintype "input"))
      (node (ref "E7") (pin "6") (pinfunction "O_6") (pintype "output"))
    )
    (net (code "77") (name "Net-(E16A-O)") (class "Default")
      (node (ref "E16") (pin "2") (pinfunction "O_2") (pintype "output"))
      (node (ref "E27") (pin "13") (pinfunction "I_13") (pintype "input"))
    )
    (net (code "78") (name "Net-(E16E-O)") (class "Default")
      (node (ref "E16") (pin "10") (pinfunction "O_10") (pintype "output"))
      (node (ref "E9") (pin "5") (pinfunction "I2_5") (pintype "input"))
    )
    (net (code "79") (name "Net-(E16F-I)") (class "Default")
      (node (ref "E16") (pin "13") (pinfunction "I_13") (pintype "input"))
      (node (ref "E31") (pin "12") (pinfunction "O_12") (pintype "output"))
    )
    (net (code "80") (name "Net-(E17A-PRE)") (class "Default")
      (node (ref "C1") (pin "1") (pinfunction "1_1") (pintype "passive"))
      (node (ref "E17") (pin "4") (pinfunction "PRE_4") (pintype "input"))
      (node (ref "R35") (pin "2") (pinfunction "2_2") (pintype "passive"))
    )
    (net (code "81") (name "Net-(E17B-CLR)") (class "Default")
      (node (ref "E17") (pin "13") (pinfunction "CLR_13") (pintype "input"))
      (node (ref "E28") (pin "2") (pinfunction "O_2") (pintype "open_collector"))
      (node (ref "E52") (pin "1") (pinfunction "O_1") (pintype "open_collector"))
      (node (ref "E53") (pin "13") (pinfunction "O_13") (pintype "open_collector"))
      (node (ref "R15") (pin "1") (pinfunction "1_1") (pintype "passive"))
    )
    (net (code "82") (name "Net-(E18A-I1)") (class "Default")
      (node (ref "E18") (pin "2") (pinfunction "I1_2") (pintype "input"))
      (node (ref "E7") (pin "8") (pinfunction "O_8") (pintype "output"))
    )
    (net (code "83") (name "Net-(E18A-O)") (class "Default")
      (node (ref "E18") (pin "3") (pinfunction "O_3") (pintype "output"))
      (node (ref "E28") (pin "11") (pinfunction "I_11") (pintype "input"))
      (node (ref "E28") (pin "13") (pinfunction "I_13") (pintype "input"))
      (node (ref "E28") (pin "9") (pinfunction "I_9") (pintype "input"))
      (node (ref "E32") (pin "4") (pinfunction "I0_4") (pintype "input"))
    )
    (net (code "84") (name "Net-(E18B-I0)") (class "Default")
      (node (ref "E18") (pin "4") (pinfunction "I0_4") (pintype "input"))
      (node (ref "E22") (pin "1") (pinfunction "O_1") (pintype "output"))
    )
    (net (code "85") (name "Net-(E18D-I0)") (class "Default")
      (node (ref "E18") (pin "12") (pinfunction "I0_12") (pintype "input"))
      (node (ref "E19") (pin "10") (pinfunction "O_10") (pintype "output"))
    )
    (net (code "86") (name "Net-(E18D-O)") (class "Default")
      (node (ref "E18") (pin "11") (pinfunction "O_11") (pintype "output"))
      (node (ref "E19") (pin "11") (pinfunction "I0_11") (pintype "input"))
    )
    (net (code "87") (name "Net-(E21A-O)") (class "Default")
      (node (ref "E21") (pin "3") (pinfunction "O_3") (pintype "output"))
      (node (ref "E26") (pin "13") (pinfunction "I_13") (pintype "input"))
    )
    (net (code "88") (name "Net-(E21B-I1)") (class "Default")
      (node (ref "E21") (pin "5") (pinfunction "I1_5") (pintype "input"))
      (node (ref "E26") (pin "5") (pinfunction "I_5") (pintype "input"))
      (node (ref "E26") (pin "8") (pinfunction "O_8") (pintype "output"))
      (node (ref "E31") (pin "11") (pinfunction "I2_11") (pintype "input"))
    )
    (net (code "89") (name "Net-(E21B-O)") (class "Default")
      (node (ref "E21") (pin "6") (pinfunction "O_6") (pintype "output"))
      (node (ref "E22") (pin "2") (pinfunction "I0_2") (pintype "input"))
      (node (ref "E22") (pin "5") (pinfunction "I0_5") (pintype "input"))
    )
    (net (code "90") (name "Net-(E21C-I0)") (class "Default")
      (node (ref "E21") (pin "9") (pinfunction "I0_9") (pintype "input"))
      (node (ref "E26") (pin "6") (pinfunction "O_6") (pintype "output"))
      (node (ref "E30") (pin "12") (pinfunction "I2_12") (pintype "input"))
    )
    (net (code "91") (name "Net-(E21D-O)") (class "Default")
      (node (ref "E21") (pin "11") (pinfunction "O_11") (pintype "output"))
      (node (ref "E9") (pin "2") (pinfunction "I1_2") (pintype "input"))
    )
    (net (code "92") (name "Net-(E22C-O)") (class "Default")
      (node (ref "E22") (pin "10") (pinfunction "O_10") (pintype "output"))
      (node (ref "E27") (pin "11") (pinfunction "I_11") (pintype "input"))
    )
    (net (code "93") (name "Net-(E23A-I1)") (class "Default")
      (node (ref "E23") (pin "3") (pinfunction "I1_3") (pintype "input"))
      (node (ref "E38") (pin "8") (pinfunction "O_8") (pintype "output"))
    )
    (net (code "94") (name "Net-(E23A-O)") (class "Default")
      (node (ref "E23") (pin "1") (pinfunction "O_1") (pintype "open_collector"))
      (node (ref "E24") (pin "12") (pinfunction "D7_12") (pintype "input"))
      (node (ref "E24") (pin "13") (pinfunction "D6_13") (pintype "input"))
      (node (ref "E24") (pin "3") (pinfunction "D1_3") (pintype "input"))
      (node (ref "E24") (pin "4") (pinfunction "D0_4") (pintype "input"))
      (node (ref "R3") (pin "1") (pinfunction "1_1") (pintype "passive"))
    )
    (net (code "95") (name "Net-(E24A-W)") (class "Default")
      (node (ref "E24") (pin "6") (pinfunction "W_6") (pintype "output"))
      (node (ref "E30") (pin "1") (pinfunction "I0_1") (pintype "input"))
      (node (ref "E30") (pin "2") (pinfunction "I1_2") (pintype "input"))
    )
    (net (code "96") (name "Net-(E25A-O)") (class "Default")
      (node (ref "E2") (pin "8") (pinfunction "I0_8") (pintype "input"))
      (node (ref "E25") (pin "1") (pinfunction "O_1") (pintype "output"))
    )
    (net (code "97") (name "Net-(E25B-I0)") (class "Default")
      (node (ref "E25") (pin "10") (pinfunction "O_10") (pintype "output"))
      (node (ref "E25") (pin "5") (pinfunction "I0_5") (pintype "input"))
    )
    (net (code "98") (name "Net-(E25B-O)") (class "Default")
      (node (ref "E2") (pin "5") (pinfunction "I0_5") (pintype "input"))
      (node (ref "E25") (pin "4") (pinfunction "O_4") (pintype "output"))
    )
    (net (code "99") (name "Net-(E26A-I)") (class "Default")
      (node (ref "E26") (pin "1") (pinfunction "I_1") (pintype "input"))
      (node (ref "E31") (pin "5") (pinfunction "I2_5") (pintype "input"))
      (node (ref "E35") (pin "11") (pinfunction "O_11") (pintype "output"))
    )
    (net (code "100") (name "Net-(E26D-I)") (class "Default")
      (node (ref "E26") (pin "9") (pinfunction "I_9") (pintype "input"))
      (node (ref "Q1") (pin "1") (pinfunction "E_1") (pintype "passive"))
      (node (ref "R37") (pin "2") (pinfunction "2_2") (pintype "passive"))
    )
    (net (code "101") (name "Net-(E30A-O)") (class "Default")
      (node (ref "E30") (pin "6") (pinfunction "O_6") (pintype "output"))
      (node (ref "E32") (pin "2") (pinfunction "I1_2") (pintype "input"))
    )
    (net (code "102") (name "Net-(E30B-O)") (class "Default")
      (node (ref "E30") (pin "8") (pinfunction "O_8") (pintype "output"))
      (node (ref "E31") (pin "4") (pinfunction "I1_4") (pintype "input"))
    )
    (net (code "103") (name "Net-(E31C-O)") (class "Default")
      (node (ref "E31") (pin "8") (pinfunction "O_8") (pintype "output"))
      (node (ref "E39") (pin "9") (pinfunction "I0_9") (pintype "input"))
    )
    (net (code "104") (name "Net-(E32A-O)") (class "Default")
      (node (ref "E32") (pin "3") (pinfunction "O_3") (pintype "output"))
      (node (ref "E33") (pin "2") (pinfunction "D_2") (pintype "input"))
    )
    (net (code "105") (name "Net-(E32B-O)") (class "Default")
      (node (ref "E32") (pin "6") (pinfunction "O_6") (pintype "output"))
      (node (ref "E36") (pin "11") (pinfunction "I_11") (pintype "input"))
    )
    (net (code "106") (name "Net-(E32D-O)") (class "Default")
      (node (ref "E32") (pin "11") (pinfunction "O_11") (pintype "output"))
      (node (ref "E38") (pin "9") (pinfunction "I0_9") (pintype "input"))
    )
    (net (code "107") (name "Net-(E33A-CLK)") (class "Default")
      (node (ref "E33") (pin "3") (pinfunction "CLK_3") (pintype "input"))
      (node (ref "E43") (pin "1") (pinfunction "O_1") (pintype "open_collector"))
      (node (ref "R34") (pin "1") (pinfunction "1_1") (pintype "passive"))
    )
    (net (code "108") (name "Net-(E33A-CLR)") (class "Default")
      (node (ref "E33") (pin "1") (pinfunction "CLR_1") (pintype "input"))
      (node (ref "E34") (pin "12") (pinfunction "O_12") (pintype "output"))
    )
    (net (code "109") (name "Net-(E33A-~{Q})") (class "Default")
      (node (ref "E33") (pin "6") (pinfunction "~{Q}_6") (pintype "output"))
      (node (ref "E37") (pin "11") (pinfunction "I0_11") (pintype "input"))
    )
    (net (code "110") (name "Net-(E34B-I)") (class "Default")
      (node (ref "E34") (pin "3") (pinfunction "I_3") (pintype "input"))
      (node (ref "E39") (pin "8") (pinfunction "O_8") (pintype "output"))
    )
    (net (code "111") (name "Net-(E35A-O)") (class "Default")
      (node (ref "E35") (pin "3") (pinfunction "O_3") (pintype "output"))
      (node (ref "E40") (pin "13") (pinfunction "CLR_13") (pintype "input"))
      (node (ref "E40") (pin "4") (pinfunction "PRE_4") (pintype "input"))
      (node (ref "E45") (pin "10") (pinfunction "PRE_10") (pintype "input"))
    )
    (net (code "112") (name "Net-(E35C-O)") (class "Default")
      (node (ref "E35") (pin "8") (pinfunction "O_8") (pintype "output"))
      (node (ref "E36") (pin "3") (pinfunction "I_3") (pintype "input"))
    )
    (net (code "113") (name "Net-(E36B-O)") (class "Default")
      (node (ref "E36") (pin "4") (pinfunction "O_4") (pintype "output"))
      (node (ref "E40") (pin "11") (pinfunction "CLK_11") (pintype "input"))
      (node (ref "E40") (pin "3") (pinfunction "CLK_3") (pintype "input"))
      (node (ref "E45") (pin "11") (pinfunction "CLK_11") (pintype "input"))
    )
    (net (code "114") (name "Net-(E37B-O)") (class "Default")
      (node (ref "E37") (pin "12") (pinfunction "I1_12") (pintype "input"))
      (node (ref "E37") (pin "4") (pinfunction "O_4") (pintype "output"))
    )
    (net (code "115") (name "Net-(E37C-O)") (class "Default")
      (node (ref "E37") (pin "10") (pinfunction "O_10") (pintype "output"))
      (node (ref "E38") (pin "13") (pinfunction "I1_13") (pintype "input"))
    )
    (net (code "116") (name "Net-(E37D-O)") (class "Default")
      (node (ref "E37") (pin "13") (pinfunction "O_13") (pintype "output"))
      (node (ref "E38") (pin "12") (pinfunction "I0_12") (pintype "input"))
    )
    (net (code "117") (name "Net-(E38A-I1)") (class "Default")
      (node (ref "E38") (pin "2") (pinfunction "I1_2") (pintype "input"))
      (node (ref "E4") (pin "1") (pinfunction "O_1") (pintype "open_collector"))
      (node (ref "E43") (pin "4") (pinfunction "O_4") (pintype "open_collector"))
      (node (ref "E5") (pin "13") (pinfunction "O_13") (pintype "open_collector"))
      (node (ref "R14") (pin "1") (pinfunction "1_1") (pintype "passive"))
    )
    (net (code "118") (name "Net-(E38A-O)") (class "Default")
      (node (ref "E3") (pin "3") (pinfunction "I1_3") (pintype "input"))
      (node (ref "E38") (pin "3") (pinfunction "O_3") (pintype "output"))
    )
    (net (code "119") (name "Net-(E38C-I1)") (class "Default")
      (node (ref "E38") (pin "10") (pinfunction "I1_10") (pintype "input"))
      (node (ref "E38") (pin "11") (pinfunction "O_11") (pintype "output"))
    )
    (net (code "120") (name "Net-(E39A-O)") (class "Default")
      (node (ref "E39") (pin "3") (pinfunction "O_3") (pintype "output"))
      (node (ref "E43") (pin "11") (pinfunction "I0_11") (pintype "input"))
      (node (ref "E43") (pin "12") (pinfunction "I1_12") (pintype "input"))
    )
    (net (code "121") (name "Net-(E40A-~{Q})") (class "Default")
      (node (ref "E40") (pin "6") (pinfunction "~{Q}_6") (pintype "output"))
      (node (ref "E44") (pin "6") (pinfunction "I1_6") (pintype "input"))
    )
    (net (code "122") (name "Net-(E40B-~{Q})") (class "Default")
      (node (ref "E40") (pin "8") (pinfunction "~{Q}_8") (pintype "output"))
      (node (ref "E44") (pin "8") (pinfunction "I0_8") (pintype "input"))
    )
    (net (code "123") (name "Net-(E42A-I1)") (class "Default")
      (node (ref "E42") (pin "2") (pinfunction "I1_2") (pintype "input"))
      (node (ref "E47") (pin "12") (pinfunction "O_12") (pintype "output"))
    )
    (net (code "124") (name "Net-(E42B-I1)") (class "Default")
      (node (ref "E42") (pin "5") (pinfunction "I1_5") (pintype "input"))
      (node (ref "E47") (pin "10") (pinfunction "O_10") (pintype "output"))
    )
    (net (code "125") (name "Net-(E42C-I0)") (class "Default")
      (node (ref "E42") (pin "9") (pinfunction "I0_9") (pintype "input"))
      (node (ref "E47") (pin "8") (pinfunction "O_8") (pintype "output"))
    )
    (net (code "126") (name "Net-(E42D-O)") (class "Default")
      (node (ref "E42") (pin "11") (pinfunction "O_11") (pintype "output"))
      (node (ref "E43") (pin "8") (pinfunction "I0_8") (pintype "input"))
    )
    (net (code "127") (name "Net-(E43A-I0)") (class "Default")
      (node (ref "E43") (pin "10") (pinfunction "O_10") (pintype "open_collector"))
      (node (ref "E43") (pin "13") (pinfunction "O_13") (pintype "open_collector"))
      (node (ref "E43") (pin "2") (pinfunction "I0_2") (pintype "input"))
      (node (ref "E43") (pin "3") (pinfunction "I1_3") (pintype "input"))
      (node (ref "R7") (pin "1") (pinfunction "1_1") (pintype "passive"))
    )
    (net (code "128") (name "Net-(E44D-I0)") (class "Default")
      (node (ref "E44") (pin "11") (pinfunction "I0_11") (pintype "input"))
      (node (ref "E45") (pin "8") (pinfunction "~{Q}_8") (pintype "output"))
    )
    (net (code "129") (name "Net-(E45A-CLK)") (class "Default")
      (node (ref "E45") (pin "3") (pinfunction "CLK_3") (pintype "input"))
      (node (ref "E47") (pin "4") (pinfunction "O_4") (pintype "output"))
      (node (ref "E50") (pin "11") (pinfunction "CLK_11") (pintype "input"))
      (node (ref "E50") (pin "3") (pinfunction "CLK_3") (pintype "input"))
    )
    (net (code "130") (name "Net-(E45A-Q)") (class "Default")
      (node (ref "E45") (pin "5") (pinfunction "Q_5") (pintype "output"))
      (node (ref "E49") (pin "5") (pinfunction "I0_5") (pintype "input"))
    )
    (net (code "131") (name "Net-(E48B-I)") (class "Default")
      (node (ref "E48") (pin "3") (pinfunction "I_3") (pintype "input"))
      (node (ref "E48") (pin "6") (pinfunction "O_6") (pintype "output"))
    )
    (net (code "132") (name "Net-(E49C-I0)") (class "Default")
      (node (ref "E49") (pin "8") (pinfunction "I0_8") (pintype "input"))
      (node (ref "E50") (pin "8") (pinfunction "~{Q}_8") (pintype "output"))
    )
    (net (code "133") (name "Net-(E49D-I0)") (class "Default")
      (node (ref "E49") (pin "11") (pinfunction "I0_11") (pintype "input"))
      (node (ref "E50") (pin "6") (pinfunction "~{Q}_6") (pintype "output"))
    )
    (net (code "134") (name "Net-(Q1-B)") (class "Default")
      (node (ref "Q1") (pin "2") (pinfunction "B_2") (pintype "passive"))
      (node (ref "R38") (pin "2") (pinfunction "2_2") (pintype "passive"))
    )
    (net (code "135") (name "OP1TS3") (class "Default")
      (node (ref "E1") (pin "9") (pinfunction "I1_9") (pintype "input"))
      (node (ref "E23") (pin "11") (pinfunction "I0_11") (pintype "input"))
      (node (ref "E23") (pin "6") (pinfunction "I1_6") (pintype "input"))
      (node (ref "E23") (pin "9") (pinfunction "I1_9") (pintype "input"))
      (node (ref "E25") (pin "13") (pinfunction "O_13") (pintype "output"))
      (node (ref "E4") (pin "9") (pinfunction "I1_9") (pintype "input"))
    )
    (net (code "136") (name "OP2TS3") (class "Default")
      (node (ref "E14") (pin "8") (pinfunction "O_8") (pintype "output"))
      (node (ref "E3") (pin "2") (pinfunction "I0_2") (pintype "input"))
    )
    (net (code "137") (name "OPE") (class "Default")
      (node (ref "E13") (pin "1") (pinfunction "I0_1") (pintype "input"))
      (node (ref "E18") (pin "10") (pinfunction "I1_10") (pintype "input"))
      (node (ref "E22") (pin "4") (pinfunction "O_4") (pintype "output"))
      (node (ref "F") (pin "E1") (pinfunction "P_E1") (pintype "passive"))
    )
    (net (code "138") (name "OPETS3") (class "Default")
      (node (ref "E14") (pin "10") (pinfunction "O_10") (pintype "output"))
      (node (ref "E21") (pin "12") (pinfunction "I0_12") (pintype "input"))
      (node (ref "E9") (pin "9") (pinfunction "I0_9") (pintype "input"))
    )
    (net (code "139") (name "OPRF") (class "Default")
      (node (ref "E11") (pin "5") (pinfunction "I2_5") (pintype "input"))
      (node (ref "E20") (pin "1") (pinfunction "I_1") (pintype "input"))
      (node (ref "E21") (pin "10") (pinfunction "I1_10") (pintype "input"))
      (node (ref "E21") (pin "4") (pinfunction "I0_4") (pintype "input"))
      (node (ref "E41") (pin "4") (pinfunction "O_4") (pintype "output"))
    )
    (net (code "140") (name "OPR_IOT") (class "Default")
      (node (ref "E11") (pin "2") (pinfunction "I1_2") (pintype "input"))
      (node (ref "E16") (pin "5") (pinfunction "I_5") (pintype "input"))
      (node (ref "E35") (pin "6") (pinfunction "O_6") (pintype "output"))
    )
    (net (code "141") (name "OV") (class "Default")
      (node (ref "E33") (pin "9") (pinfunction "Q_9") (pintype "output"))
      (node (ref "E52") (pin "5") (pinfunction "I0_5") (pintype "input"))
      (node (ref "E52") (pin "8") (pinfunction "I0_8") (pintype "input"))
    )
    (net (code "142") (name "PAGEZ") (class "Default")
      (node (ref "E36") (pin "10") (pinfunction "O_10") (pintype "output"))
      (node (ref "H") (pin "C1") (pinfunction "P_C1") (pintype "passive"))
    )
    (net (code "143") (name "PULSE_LA") (class "Default")
      (node (ref "E52") (pin "11") (pinfunction "I0_11") (pintype "input"))
      (node (ref "U$2") (pin "DR2") (pinfunction "1_DR2") (pintype "bidirectional"))
    )
    (net (code "144") (name "PWR_OK") (class "Default")
      (node (ref "E6") (pin "5") (pinfunction "I_5") (pintype "input"))
      (node (ref "U$2") (pin "BV2") (pinfunction "1_BV2") (pintype "bidirectional"))
    )
    (net (code "145") (name "RUN") (class "Default")
      (node (ref "E15") (pin "3") (pinfunction "I1_3") (pintype "input"))
      (node (ref "U$2") (pin "BU2") (pinfunction "1_BU2") (pintype "bidirectional"))
    )
    (net (code "146") (name "SKIP1") (class "Default")
      (node (ref "E17") (pin "9") (pinfunction "Q_9") (pintype "output"))
      (node (ref "E2") (pin "12") (pinfunction "I1_12") (pintype "input"))
      (node (ref "E2") (pin "2") (pinfunction "I0_2") (pintype "input"))
    )
    (net (code "147") (name "TADETS3") (class "Default")
      (node (ref "E10") (pin "11") (pinfunction "I_11") (pintype "input"))
      (node (ref "E10") (pin "13") (pinfunction "I_13") (pintype "input"))
      (node (ref "E51") (pin "4") (pinfunction "O_4") (pintype "output"))
      (node (ref "E8") (pin "11") (pinfunction "I_11") (pintype "input"))
    )
    (net (code "148") (name "TP1") (class "Default")
      (node (ref "E52") (pin "3") (pinfunction "I1_3") (pintype "input"))
      (node (ref "E53") (pin "6") (pinfunction "I1_6") (pintype "input"))
      (node (ref "U$2") (pin "CD2") (pinfunction "1_CD2") (pintype "bidirectional"))
    )
    (net (code "149") (name "TP2") (class "Default")
      (node (ref "E29") (pin "12") (pinfunction "I1_12") (pintype "input"))
      (node (ref "U$2") (pin "CE2") (pinfunction "1_CE2") (pintype "bidirectional"))
    )
    (net (code "150") (name "TP3") (class "Default")
      (node (ref "E48") (pin "5") (pinfunction "I_5") (pintype "input"))
      (node (ref "U$2") (pin "CH2") (pinfunction "1_CH2") (pintype "bidirectional"))
    )
    (net (code "151") (name "TP4") (class "Default")
      (node (ref "E17") (pin "3") (pinfunction "CLK_3") (pintype "input"))
      (node (ref "E21") (pin "2") (pinfunction "I1_2") (pintype "input"))
      (node (ref "U$2") (pin "CJ2") (pinfunction "1_CJ2") (pintype "bidirectional"))
    )
    (net (code "152") (name "TP4~{MALC}") (class "Default")
      (node (ref "E26") (pin "12") (pinfunction "O_12") (pintype "output"))
      (node (ref "E27") (pin "1") (pinfunction "I_1") (pintype "input"))
      (node (ref "E35") (pin "1") (pinfunction "I0_1") (pintype "input"))
    )
    (net (code "153") (name "TS4FSET~{MS_DIS}") (class "Default")
      (node (ref "E1") (pin "6") (pinfunction "I1_6") (pintype "input"))
      (node (ref "E16") (pin "12") (pinfunction "O_12") (pintype "output"))
      (node (ref "E2") (pin "3") (pinfunction "I1_3") (pintype "input"))
    )
    (net (code "154") (name "VCC") (class "Default")
      (node (ref "C10") (pin "1") (pinfunction "1_1") (pintype "passive"))
      (node (ref "C11") (pin "1") (pinfunction "1_1") (pintype "passive"))
      (node (ref "C12") (pin "1") (pinfunction "1_1") (pintype "passive"))
      (node (ref "C13") (pin "1") (pinfunction "1_1") (pintype "passive"))
      (node (ref "C14") (pin "1") (pinfunction "1_1") (pintype "passive"))
      (node (ref "C15") (pin "1") (pinfunction "1_1") (pintype "passive"))
      (node (ref "C16") (pin "1") (pinfunction "1_1") (pintype "passive"))
      (node (ref "C17") (pin "1") (pinfunction "1_1") (pintype "passive"))
      (node (ref "C18") (pin "1") (pinfunction "1_1") (pintype "passive"))
      (node (ref "C19") (pin "1") (pinfunction "1_1") (pintype "passive"))
      (node (ref "C2") (pin "1") (pinfunction "1_1") (pintype "passive"))
      (node (ref "C20") (pin "1") (pinfunction "1_1") (pintype "passive"))
      (node (ref "C21") (pin "1") (pinfunction "1_1") (pintype "passive"))
      (node (ref "C22") (pin "1") (pinfunction "1_1") (pintype "passive"))
      (node (ref "C23") (pin "1") (pinfunction "1_1") (pintype "passive"))
      (node (ref "C24") (pin "1") (pinfunction "1_1") (pintype "passive"))
      (node (ref "C25") (pin "1") (pinfunction "1_1") (pintype "passive"))
      (node (ref "C26") (pin "1") (pinfunction "1_1") (pintype "passive"))
      (node (ref "C27") (pin "+") (pinfunction "+_+") (pintype "passive"))
      (node (ref "C29") (pin "+") (pinfunction "+_+") (pintype "passive"))
      (node (ref "C3") (pin "1") (pinfunction "1_1") (pintype "passive"))
      (node (ref "C30") (pin "1") (pinfunction "1_1") (pintype "passive"))
      (node (ref "C31") (pin "1") (pinfunction "1_1") (pintype "passive"))
      (node (ref "C32") (pin "1") (pinfunction "1_1") (pintype "passive"))
      (node (ref "C33") (pin "1") (pinfunction "1_1") (pintype "passive"))
      (node (ref "C4") (pin "1") (pinfunction "1_1") (pintype "passive"))
      (node (ref "C6") (pin "1") (pinfunction "1_1") (pintype "passive"))
      (node (ref "C7") (pin "1") (pinfunction "1_1") (pintype "passive"))
      (node (ref "C8") (pin "1") (pinfunction "1_1") (pintype "passive"))
      (node (ref "C9") (pin "1") (pinfunction "1_1") (pintype "passive"))
      (node (ref "Q1") (pin "3") (pinfunction "C_3") (pintype "passive"))
      (node (ref "R1") (pin "2") (pinfunction "2_2") (pintype "passive"))
      (node (ref "R10") (pin "2") (pinfunction "2_2") (pintype "passive"))
      (node (ref "R11") (pin "2") (pinfunction "2_2") (pintype "passive"))
      (node (ref "R12") (pin "2") (pinfunction "2_2") (pintype "passive"))
      (node (ref "R13") (pin "2") (pinfunction "2_2") (pintype "passive"))
      (node (ref "R14") (pin "2") (pinfunction "2_2") (pintype "passive"))
      (node (ref "R15") (pin "2") (pinfunction "2_2") (pintype "passive"))
      (node (ref "R16") (pin "2") (pinfunction "2_2") (pintype "passive"))
      (node (ref "R17") (pin "2") (pinfunction "2_2") (pintype "passive"))
      (node (ref "R19") (pin "2") (pinfunction "2_2") (pintype "passive"))
      (node (ref "R2") (pin "2") (pinfunction "2_2") (pintype "passive"))
      (node (ref "R20") (pin "2") (pinfunction "2_2") (pintype "passive"))
      (node (ref "R21") (pin "2") (pinfunction "2_2") (pintype "passive"))
      (node (ref "R22") (pin "2") (pinfunction "2_2") (pintype "passive"))
      (node (ref "R23") (pin "2") (pinfunction "2_2") (pintype "passive"))
      (node (ref "R24") (pin "2") (pinfunction "2_2") (pintype "passive"))
      (node (ref "R25") (pin "2") (pinfunction "2_2") (pintype "passive"))
      (node (ref "R26") (pin "2") (pinfunction "2_2") (pintype "passive"))
      (node (ref "R27") (pin "2") (pinfunction "2_2") (pintype "passive"))
      (node (ref "R28") (pin "2") (pinfunction "2_2") (pintype "passive"))
      (node (ref "R29") (pin "2") (pinfunction "2_2") (pintype "passive"))
      (node (ref "R3") (pin "2") (pinfunction "2_2") (pintype "passive"))
      (node (ref "R30") (pin "2") (pinfunction "2_2") (pintype "passive"))
      (node (ref "R31") (pin "2") (pinfunction "2_2") (pintype "passive"))
      (node (ref "R32") (pin "2") (pinfunction "2_2") (pintype "passive"))
      (node (ref "R33") (pin "2") (pinfunction "2_2") (pintype "passive"))
      (node (ref "R34") (pin "2") (pinfunction "2_2") (pintype "passive"))
      (node (ref "R36") (pin "2") (pinfunction "2_2") (pintype "passive"))
      (node (ref "R4") (pin "2") (pinfunction "2_2") (pintype "passive"))
      (node (ref "R5") (pin "2") (pinfunction "2_2") (pintype "passive"))
      (node (ref "R6") (pin "2") (pinfunction "2_2") (pintype "passive"))
      (node (ref "R7") (pin "2") (pinfunction "2_2") (pintype "passive"))
      (node (ref "R8") (pin "2") (pinfunction "2_2") (pintype "passive"))
      (node (ref "R9") (pin "2") (pinfunction "2_2") (pintype "passive"))
      (node (ref "U$2") (pin "AA2") (pinfunction "1_AA2") (pintype "bidirectional"))
      (node (ref "U$2") (pin "BA2") (pinfunction "1_BA2") (pintype "bidirectional"))
      (node (ref "U$2") (pin "CA2") (pinfunction "1_CA2") (pintype "bidirectional"))
    )
    (net (code "155") (name "unconnected-(E13C-O-Pad8)") (class "Default")
      (node (ref "E13") (pin "8") (pinfunction "O_8") (pintype "open_collector"))
    )
    (net (code "156") (name "unconnected-(E17A-Q-Pad5)") (class "Default")
      (node (ref "E17") (pin "5") (pinfunction "Q_5") (pintype "output"))
    )
    (net (code "157") (name "unconnected-(E24A-Y-Pad5)") (class "Default")
      (node (ref "E24") (pin "5") (pinfunction "Y_5") (pintype "output"))
    )
    (net (code "158") (name "unconnected-(E33B-~{Q}-Pad8)") (class "Default")
      (node (ref "E33") (pin "8") (pinfunction "~{Q}_8") (pintype "output"))
    )
    (net (code "159") (name "unconnected-(E40A-Q-Pad5)") (class "Default")
      (node (ref "E40") (pin "5") (pinfunction "Q_5") (pintype "output"))
    )
    (net (code "160") (name "unconnected-(E40B-Q-Pad9)") (class "Default")
      (node (ref "E40") (pin "9") (pinfunction "Q_9") (pintype "output"))
    )
    (net (code "161") (name "unconnected-(E45A-~{Q}-Pad6)") (class "Default")
      (node (ref "E45") (pin "6") (pinfunction "~{Q}_6") (pintype "output"))
    )
    (net (code "162") (name "unconnected-(E45B-Q-Pad9)") (class "Default")
      (node (ref "E45") (pin "9") (pinfunction "Q_9") (pintype "output"))
    )
    (net (code "163") (name "unconnected-(E46A-8-Pad6)") (class "Default")
      (node (ref "E46") (pin "6") (pinfunction "8_6") (pintype "output"))
    )
    (net (code "164") (name "unconnected-(E46A-9-Pad7)") (class "Default")
      (node (ref "E46") (pin "7") (pinfunction "9_7") (pintype "output"))
    )
    (net (code "165") (name "unconnected-(E50A-Q-Pad5)") (class "Default")
      (node (ref "E50") (pin "5") (pinfunction "Q_5") (pintype "output"))
    )
    (net (code "166") (name "unconnected-(E50B-Q-Pad9)") (class "Default")
      (node (ref "E50") (pin "9") (pinfunction "Q_9") (pintype "output"))
    )
    (net (code "167") (name "~{AC0EQAC1}") (class "Default")
      (node (ref "E38") (pin "6") (pinfunction "O_6") (pintype "output"))
      (node (ref "F") (pin "F1") (pinfunction "P_F1") (pintype "passive"))
    )
    (net (code "168") (name "~{AC2BUS}") (class "Default")
      (node (ref "E") (pin "T2") (pinfunction "P_T2") (pintype "passive"))
      (node (ref "E10") (pin "12") (pinfunction "O_12") (pintype "open_collector"))
      (node (ref "E10") (pin "2") (pinfunction "O_2") (pintype "open_collector"))
      (node (ref "E2") (pin "10") (pinfunction "O_10") (pintype "open_collector"))
      (node (ref "E2") (pin "4") (pinfunction "O_4") (pintype "open_collector"))
      (node (ref "E5") (pin "1") (pinfunction "O_1") (pintype "open_collector"))
      (node (ref "E9") (pin "12") (pinfunction "O_12") (pintype "open_collector"))
      (node (ref "F") (pin "U1") (pinfunction "P_U1") (pintype "passive"))
      (node (ref "R27") (pin "1") (pinfunction "1_1") (pintype "passive"))
    )
    (net (code "169") (name "~{AC2_AC3}") (class "Default")
      (node (ref "E18") (pin "13") (pinfunction "I1_13") (pintype "input"))
      (node (ref "E19") (pin "4") (pinfunction "O_4") (pintype "output"))
      (node (ref "F") (pin "F2") (pinfunction "P_F2") (pintype "passive"))
    )
    (net (code "170") (name "~{AC04-11EQ0}") (class "Default")
      (node (ref "E") (pin "B1") (pinfunction "P_B1") (pintype "passive"))
      (node (ref "E19") (pin "12") (pinfunction "I1_12") (pintype "input"))
      (node (ref "F") (pin "P1") (pinfunction "P_P1") (pintype "passive"))
    )
    (net (code "171") (name "~{AC_LOAD}") (class "Default")
      (node (ref "E") (pin "L1") (pinfunction "P_L1") (pintype "passive"))
      (node (ref "E15") (pin "10") (pinfunction "O_10") (pintype "open_collector"))
      (node (ref "E15") (pin "13") (pinfunction "O_13") (pintype "open_collector"))
      (node (ref "F") (pin "K2") (pinfunction "P_K2") (pintype "passive"))
      (node (ref "R12") (pin "1") (pinfunction "1_1") (pintype "passive"))
    )
    (net (code "172") (name "~{AD00}") (class "Default")
      (node (ref "E24") (pin "14") (pinfunction "D5_14") (pintype "input"))
      (node (ref "F") (pin "H1") (pinfunction "P_H1") (pintype "passive"))
      (node (ref "H") (pin "P1") (pinfunction "P_P1") (pintype "passive"))
    )
    (net (code "173") (name "~{AD01}") (class "Default")
      (node (ref "E24") (pin "15") (pinfunction "D4_15") (pintype "input"))
      (node (ref "H") (pin "R1") (pinfunction "P_R1") (pintype "passive"))
    )
    (net (code "174") (name "~{AD10}") (class "Default")
      (node (ref "E24") (pin "2") (pinfunction "D2_2") (pintype "input"))
      (node (ref "H") (pin "M1") (pinfunction "P_M1") (pintype "passive"))
    )
    (net (code "175") (name "~{AD11}") (class "Default")
      (node (ref "E24") (pin "1") (pinfunction "D3_1") (pintype "input"))
      (node (ref "H") (pin "N1") (pinfunction "P_N1") (pintype "passive"))
    )
    (net (code "176") (name "~{ADLK}") (class "Default")
      (node (ref "F") (pin "J1") (pinfunction "P_J1") (pintype "passive"))
      (node (ref "H") (pin "L1") (pinfunction "P_L1") (pintype "passive"))
    )
    (net (code "177") (name "~{AD_LD_D15}") (class "Default")
      (node (ref "E32") (pin "10") (pinfunction "I1_10") (pintype "input"))
      (node (ref "R9") (pin "1") (pinfunction "1_1") (pintype "passive"))
    )
    (net (code "178") (name "~{AL2MQ_ENA}") (class "Default")
      (node (ref "E") (pin "T1") (pinfunction "P_T1") (pintype "passive"))
      (node (ref "F") (pin "L2") (pinfunction "P_L2") (pintype "passive"))
    )
    (net (code "179") (name "~{ANDE}") (class "Default")
      (node (ref "E42") (pin "3") (pinfunction "O_3") (pintype "output"))
      (node (ref "E7") (pin "4") (pinfunction "I2_4") (pintype "input"))
    )
    (net (code "180") (name "~{AND}") (class "Default")
      (node (ref "E46") (pin "5") (pinfunction "7_5") (pintype "output"))
      (node (ref "E47") (pin "13") (pinfunction "I_13") (pintype "input"))
      (node (ref "E51") (pin "3") (pinfunction "I1_3") (pintype "input"))
    )
    (net (code "181") (name "~{BK_DC}") (class "Default")
      (node (ref "E4") (pin "6") (pinfunction "I1_6") (pintype "input"))
      (node (ref "U$2") (pin "BK2") (pinfunction "1_BK2") (pintype "bidirectional"))
    )
    (net (code "182") (name "~{BUS_STROBE}") (class "Default")
      (node (ref "E20") (pin "11") (pinfunction "I_11") (pintype "input"))
      (node (ref "U$2") (pin "CK1") (pinfunction "1_CK1") (pintype "bidirectional"))
    )
    (net (code "183") (name "~{C0}") (class "Default")
      (node (ref "E16") (pin "3") (pinfunction "I_3") (pintype "input"))
      (node (ref "E25") (pin "8") (pinfunction "I0_8") (pintype "input"))
      (node (ref "U$2") (pin "CE1") (pinfunction "1_CE1") (pintype "bidirectional"))
    )
    (net (code "184") (name "~{C1}") (class "Default")
      (node (ref "E1") (pin "12") (pinfunction "I1_12") (pintype "input"))
      (node (ref "E12") (pin "13") (pinfunction "I2_13") (pintype "input"))
      (node (ref "E25") (pin "9") (pinfunction "I1_9") (pintype "input"))
      (node (ref "U$2") (pin "CH1") (pinfunction "1_CH1") (pintype "bidirectional"))
    )
    (net (code "185") (name "~{C2}") (class "Default")
      (node (ref "E12") (pin "2") (pinfunction "I1_2") (pintype "input"))
      (node (ref "E15") (pin "11") (pinfunction "I0_11") (pintype "input"))
      (node (ref "E2") (pin "6") (pinfunction "I1_6") (pintype "input"))
      (node (ref "E20") (pin "9") (pinfunction "I_9") (pintype "input"))
      (node (ref "E22") (pin "12") (pinfunction "I1_12") (pintype "input"))
      (node (ref "U$2") (pin "CJ1") (pinfunction "1_CJ1") (pintype "bidirectional"))
    )
    (net (code "186") (name "~{CARRY_IN}") (class "Default")
      (node (ref "E11") (pin "8") (pinfunction "O_8") (pintype "open_collector"))
      (node (ref "E2") (pin "1") (pinfunction "O_1") (pintype "open_collector"))
      (node (ref "E2") (pin "13") (pinfunction "O_13") (pintype "open_collector"))
      (node (ref "E3") (pin "10") (pinfunction "O_10") (pintype "open_collector"))
      (node (ref "E4") (pin "10") (pinfunction "O_10") (pintype "open_collector"))
      (node (ref "E5") (pin "10") (pinfunction "O_10") (pintype "open_collector"))
      (node (ref "E8") (pin "12") (pinfunction "O_12") (pintype "open_collector"))
      (node (ref "F") (pin "S1") (pinfunction "P_S1") (pintype "passive"))
      (node (ref "H") (pin "M2") (pinfunction "P_M2") (pintype "passive"))
      (node (ref "R28") (pin "1") (pinfunction "1_1") (pintype "passive"))
    )
    (net (code "187") (name "~{CARRY_OUT}") (class "Default")
      (node (ref "E") (pin "C1") (pinfunction "P_C1") (pintype "passive"))
      (node (ref "E32") (pin "12") (pinfunction "I0_12") (pintype "input"))
      (node (ref "E32") (pin "13") (pinfunction "I1_13") (pintype "input"))
      (node (ref "E33") (pin "12") (pinfunction "D_12") (pintype "input"))
      (node (ref "F") (pin "M2") (pinfunction "P_M2") (pintype "passive"))
    )
    (net (code "188") (name "~{CPMA_DIS}") (class "Default")
      (node (ref "E11") (pin "10") (pinfunction "I1_10") (pintype "input"))
      (node (ref "E17") (pin "2") (pinfunction "D_2") (pintype "input"))
      (node (ref "U$2") (pin "CU1") (pinfunction "1_CU1") (pintype "bidirectional"))
    )
    (net (code "189") (name "~{CPMA_LOAD}") (class "Default")
      (node (ref "E27") (pin "2") (pinfunction "O_2") (pintype "open_collector"))
      (node (ref "E47") (pin "3") (pinfunction "I_3") (pintype "input"))
      (node (ref "E52") (pin "13") (pinfunction "O_13") (pintype "open_collector"))
      (node (ref "H") (pin "E1") (pinfunction "P_E1") (pintype "passive"))
      (node (ref "R11") (pin "1") (pinfunction "1_1") (pintype "passive"))
    )
    (net (code "190") (name "~{DCAE}") (class "Default")
      (node (ref "E42") (pin "6") (pinfunction "O_6") (pintype "output"))
      (node (ref "E7") (pin "2") (pinfunction "I1_2") (pintype "input"))
    )
    (net (code "191") (name "~{DCA}") (class "Default")
      (node (ref "E41") (pin "8") (pinfunction "I0_8") (pintype "input"))
      (node (ref "E46") (pin "12") (pinfunction "1_12") (pintype "output"))
      (node (ref "E47") (pin "11") (pinfunction "I_11") (pintype "input"))
    )
    (net (code "192") (name "~{DSET}") (class "Default")
      (node (ref "E34") (pin "4") (pinfunction "O_4") (pintype "output"))
      (node (ref "E49") (pin "2") (pinfunction "I0_2") (pintype "input"))
      (node (ref "E50") (pin "12") (pinfunction "D_12") (pintype "input"))
    )
    (net (code "193") (name "~{D}") (class "Default")
      (node (ref "E34") (pin "5") (pinfunction "I_5") (pintype "input"))
      (node (ref "E49") (pin "10") (pinfunction "O_10") (pintype "open_collector"))
    )
    (net (code "194") (name "~{ESET}") (class "Default")
      (node (ref "E36") (pin "8") (pinfunction "O_8") (pintype "output"))
      (node (ref "E49") (pin "3") (pinfunction "I1_3") (pintype "input"))
    )
    (net (code "195") (name "~{ETS2}") (class "Default")
      (node (ref "E29") (pin "3") (pinfunction "O_3") (pintype "output"))
      (node (ref "E41") (pin "3") (pinfunction "I1_3") (pintype "input"))
      (node (ref "E41") (pin "9") (pinfunction "I1_9") (pintype "input"))
      (node (ref "E51") (pin "8") (pinfunction "I0_8") (pintype "input"))
    )
    (net (code "196") (name "~{ETS3}") (class "Default")
      (node (ref "E29") (pin "14") (pinfunction "O_14") (pintype "output"))
      (node (ref "E41") (pin "12") (pinfunction "I1_12") (pintype "input"))
      (node (ref "E51") (pin "12") (pinfunction "I1_12") (pintype "input"))
      (node (ref "E51") (pin "2") (pinfunction "I0_2") (pintype "input"))
      (node (ref "E51") (pin "5") (pinfunction "I0_5") (pintype "input"))
    )
    (net (code "197") (name "~{E}") (class "Default")
      (node (ref "E29") (pin "10") (pinfunction "I1_10") (pintype "input"))
      (node (ref "E29") (pin "5") (pinfunction "I1_5") (pintype "input"))
      (node (ref "E37") (pin "2") (pinfunction "I0_2") (pintype "input"))
      (node (ref "E47") (pin "1") (pinfunction "I_1") (pintype "input"))
      (node (ref "E49") (pin "4") (pinfunction "O_4") (pintype "open_collector"))
    )
    (net (code "198") (name "~{FDSET}") (class "Default")
      (node (ref "E39") (pin "10") (pinfunction "I1_10") (pintype "input"))
      (node (ref "E39") (pin "12") (pinfunction "I0_12") (pintype "input"))
      (node (ref "F") (pin "L1") (pinfunction "P_L1") (pintype "passive"))
      (node (ref "R29") (pin "1") (pinfunction "1_1") (pintype "passive"))
    )
    (net (code "199") (name "~{FESET}") (class "Default")
      (node (ref "E27") (pin "8") (pinfunction "O_8") (pintype "open_collector"))
      (node (ref "E31") (pin "3") (pinfunction "I0_3") (pintype "input"))
      (node (ref "E39") (pin "13") (pinfunction "I1_13") (pintype "input"))
      (node (ref "F") (pin "M1") (pinfunction "P_M1") (pintype "passive"))
      (node (ref "R16") (pin "1") (pinfunction "1_1") (pintype "passive"))
    )
    (net (code "200") (name "~{FE_FD}") (class "Default")
      (node (ref "E1") (pin "5") (pinfunction "I0_5") (pintype "input"))
      (node (ref "E27") (pin "4") (pinfunction "O_4") (pintype "open_collector"))
      (node (ref "E7") (pin "10") (pinfunction "I1_10") (pintype "input"))
      (node (ref "R10") (pin "1") (pinfunction "1_1") (pintype "passive"))
    )
    (net (code "201") (name "~{FSET}") (class "Default")
      (node (ref "E36") (pin "1") (pinfunction "I_1") (pintype "input"))
      (node (ref "E49") (pin "1") (pinfunction "O_1") (pintype "open_collector"))
      (node (ref "E50") (pin "2") (pinfunction "D_2") (pintype "input"))
      (node (ref "E7") (pin "12") (pinfunction "I2_12") (pintype "input"))
      (node (ref "U$2") (pin "DP2") (pinfunction "1_DP2") (pintype "bidirectional"))
    )
    (net (code "202") (name "~{F}") (class "Default")
      (node (ref "E34") (pin "1") (pinfunction "I_1") (pintype "input"))
      (node (ref "E39") (pin "4") (pinfunction "I0_4") (pintype "input"))
      (node (ref "E41") (pin "6") (pinfunction "I1_6") (pintype "input"))
      (node (ref "E49") (pin "13") (pinfunction "O_13") (pintype "open_collector"))
    )
    (net (code "203") (name "~{IOT}") (class "Default")
      (node (ref "E32") (pin "9") (pinfunction "I0_9") (pintype "input"))
      (node (ref "E35") (pin "5") (pinfunction "I1_5") (pintype "input"))
      (node (ref "E46") (pin "9") (pinfunction "4_9") (pintype "output"))
    )
    (net (code "204") (name "~{IR0}") (class "Default")
      (node (ref "E44") (pin "10") (pinfunction "O_10") (pintype "open_collector"))
      (node (ref "E46") (pin "15") (pinfunction "A_15") (pintype "input"))
      (node (ref "U$2") (pin "DD2") (pinfunction "1_DD2") (pintype "bidirectional"))
    )
    (net (code "205") (name "~{IR1}") (class "Default")
      (node (ref "E44") (pin "13") (pinfunction "O_13") (pintype "open_collector"))
      (node (ref "E46") (pin "14") (pinfunction "B_14") (pintype "input"))
      (node (ref "U$2") (pin "DE2") (pinfunction "1_DE2") (pintype "bidirectional"))
    )
    (net (code "206") (name "~{IR2}") (class "Default")
      (node (ref "E44") (pin "4") (pinfunction "O_4") (pintype "open_collector"))
      (node (ref "E46") (pin "1") (pinfunction "C_1") (pintype "input"))
      (node (ref "U$2") (pin "DH2") (pinfunction "1_DH2") (pintype "bidirectional"))
    )
    (net (code "207") (name "~{ISZ}") (class "Default")
      (node (ref "E46") (pin "3") (pinfunction "5_3") (pintype "output"))
      (node (ref "E51") (pin "11") (pinfunction "I0_11") (pintype "input"))
      (node (ref "E51") (pin "9") (pinfunction "I1_9") (pintype "input"))
    )
    (net (code "208") (name "~{JMP}") (class "Default")
      (node (ref "E26") (pin "3") (pinfunction "I_3") (pintype "input"))
      (node (ref "E30") (pin "13") (pinfunction "I3_13") (pintype "input"))
      (node (ref "E35") (pin "12") (pinfunction "I0_12") (pintype "input"))
      (node (ref "E46") (pin "11") (pinfunction "2_11") (pintype "output"))
    )
    (net (code "209") (name "~{JMS}") (class "Default")
      (node (ref "E37") (pin "3") (pinfunction "I1_3") (pintype "input"))
      (node (ref "E41") (pin "11") (pinfunction "I0_11") (pintype "input"))
      (node (ref "E41") (pin "2") (pinfunction "I0_2") (pintype "input"))
      (node (ref "E46") (pin "4") (pinfunction "6_4") (pintype "output"))
    )
    (net (code "210") (name "~{KEYCONTROL}") (class "Default")
      (node (ref "E39") (pin "5") (pinfunction "I1_5") (pintype "input"))
      (node (ref "E47") (pin "5") (pinfunction "I_5") (pintype "input"))
      (node (ref "E52") (pin "12") (pinfunction "I1_12") (pintype "input"))
      (node (ref "U$2") (pin "DU2") (pinfunction "1_DU2") (pintype "bidirectional"))
    )
    (net (code "211") (name "~{LA_ENABLE}") (class "Default")
      (node (ref "E16") (pin "1") (pinfunction "I_1") (pintype "input"))
      (node (ref "U$2") (pin "BM2") (pinfunction "1_BM2") (pintype "bidirectional"))
    )
    (net (code "212") (name "~{LEFT}") (class "Default")
      (node (ref "E23") (pin "10") (pinfunction "O_10") (pintype "open_collector"))
      (node (ref "E24") (pin "10") (pinfunction "B_10") (pintype "input"))
      (node (ref "E28") (pin "6") (pinfunction "O_6") (pintype "open_collector"))
      (node (ref "E28") (pin "8") (pinfunction "O_8") (pintype "open_collector"))
      (node (ref "F") (pin "D1") (pinfunction "P_D1") (pintype "passive"))
      (node (ref "H") (pin "J2") (pinfunction "P_J2") (pintype "passive"))
      (node (ref "R5") (pin "1") (pinfunction "1_1") (pintype "passive"))
    )
    (net (code "213") (name "~{LINK_DATA}") (class "Default")
      (node (ref "E32") (pin "1") (pinfunction "I0_1") (pintype "input"))
      (node (ref "R1") (pin "1") (pinfunction "1_1") (pintype "passive"))
    )
    (net (code "214") (name "~{LINK_LOAD}") (class "Default")
      (node (ref "E39") (pin "1") (pinfunction "I0_1") (pintype "input"))
      (node (ref "E39") (pin "2") (pinfunction "I1_2") (pintype "input"))
      (node (ref "U$2") (pin "CS2") (pinfunction "1_CS2") (pintype "bidirectional"))
    )
    (net (code "215") (name "~{LINK}") (class "Default")
      (node (ref "E4") (pin "13") (pinfunction "O_13") (pintype "open_collector"))
      (node (ref "R25") (pin "1") (pinfunction "1_1") (pintype "passive"))
      (node (ref "U$2") (pin "AV2") (pinfunction "1_AV2") (pintype "bidirectional"))
    )
    (net (code "216") (name "~{MAC}") (class "Default")
      (node (ref "E17") (pin "6") (pinfunction "~{Q}_6") (pintype "output"))
      (node (ref "H") (pin "A1") (pinfunction "P_A1") (pintype "passive"))
    )
    (net (code "217") (name "~{MALC}") (class "Default")
      (node (ref "E21") (pin "1") (pinfunction "I0_1") (pintype "input"))
      (node (ref "U$2") (pin "BH2") (pinfunction "1_BH2") (pintype "bidirectional"))
    )
    (net (code "218") (name "~{MB_LOAD}") (class "Default")
      (node (ref "E48") (pin "2") (pinfunction "O_2") (pintype "output"))
      (node (ref "H") (pin "F1") (pinfunction "P_F1") (pintype "passive"))
    )
    (net (code "219") (name "~{MD00}") (class "Default")
      (node (ref "E40") (pin "12") (pinfunction "D_12") (pintype "input"))
      (node (ref "U$2") (pin "AK1") (pinfunction "1_AK1") (pintype "bidirectional"))
    )
    (net (code "220") (name "~{MD01}") (class "Default")
      (node (ref "E45") (pin "12") (pinfunction "D_12") (pintype "input"))
      (node (ref "U$2") (pin "AL1") (pinfunction "1_AL1") (pintype "bidirectional"))
    )
    (net (code "221") (name "~{MD02}") (class "Default")
      (node (ref "E40") (pin "2") (pinfunction "D_2") (pintype "input"))
      (node (ref "U$2") (pin "AM1") (pinfunction "1_AM1") (pintype "bidirectional"))
    )
    (net (code "222") (name "~{MD03}") (class "Default")
      (node (ref "R38") (pin "1") (pinfunction "1_1") (pintype "passive"))
      (node (ref "U$2") (pin "AP1") (pinfunction "1_AP1") (pintype "bidirectional"))
    )
    (net (code "223") (name "~{MD04}") (class "Default")
      (node (ref "E11") (pin "4") (pinfunction "I1_4") (pintype "input"))
      (node (ref "E32") (pin "5") (pinfunction "I1_5") (pintype "input"))
      (node (ref "U$2") (pin "BK1") (pinfunction "1_BK1") (pintype "bidirectional"))
    )
    (net (code "224") (name "~{MD05}") (class "Default")
      (node (ref "E20") (pin "13") (pinfunction "I_13") (pintype "input"))
      (node (ref "E37") (pin "6") (pinfunction "I1_6") (pintype "input"))
      (node (ref "U$2") (pin "BL1") (pinfunction "1_BL1") (pintype "bidirectional"))
    )
    (net (code "225") (name "~{MD06}") (class "Default")
      (node (ref "E20") (pin "3") (pinfunction "I_3") (pintype "input"))
      (node (ref "U$2") (pin "BM1") (pinfunction "1_BM1") (pintype "bidirectional"))
    )
    (net (code "226") (name "~{MD07}") (class "Default")
      (node (ref "E20") (pin "5") (pinfunction "I_5") (pintype "input"))
      (node (ref "E37") (pin "8") (pinfunction "I0_8") (pintype "input"))
      (node (ref "U$2") (pin "BP1") (pinfunction "1_BP1") (pintype "bidirectional"))
    )
    (net (code "227") (name "~{MD08}") (class "Default")
      (node (ref "E38") (pin "1") (pinfunction "I0_1") (pintype "input"))
      (node (ref "E48") (pin "13") (pinfunction "I_13") (pintype "input"))
      (node (ref "U$2") (pin "DK1") (pinfunction "1_DK1") (pintype "bidirectional"))
    )
    (net (code "228") (name "~{MD09}") (class "Default")
      (node (ref "E48") (pin "11") (pinfunction "I_11") (pintype "input"))
      (node (ref "U$2") (pin "DL1") (pinfunction "1_DL1") (pintype "bidirectional"))
    )
    (net (code "229") (name "~{MD10}") (class "Default")
      (node (ref "E48") (pin "9") (pinfunction "I_9") (pintype "input"))
      (node (ref "U$2") (pin "DM1") (pinfunction "1_DM1") (pintype "bidirectional"))
    )
    (net (code "230") (name "~{MD11}") (class "Default")
      (node (ref "E22") (pin "6") (pinfunction "I1_6") (pintype "input"))
      (node (ref "E26") (pin "11") (pinfunction "I_11") (pintype "input"))
      (node (ref "U$2") (pin "DP1") (pinfunction "1_DP1") (pintype "bidirectional"))
    )
    (net (code "231") (name "~{MQ00-03EQ0}") (class "Default")
      (node (ref "E") (pin "A1") (pinfunction "P_A1") (pintype "passive"))
      (node (ref "E19") (pin "3") (pinfunction "I1_3") (pintype "input"))
    )
    (net (code "232") (name "~{MQ00}") (class "Default")
      (node (ref "F") (pin "A2") (pinfunction "P_A2") (pintype "passive"))
      (node (ref "H") (pin "V2") (pinfunction "P_V2") (pintype "passive"))
    )
    (net (code "233") (name "~{MQ2BUS}") (class "Default")
      (node (ref "E") (pin "D2") (pinfunction "P_D2") (pintype "passive"))
      (node (ref "E9") (pin "6") (pinfunction "O_6") (pintype "open_collector"))
      (node (ref "E9") (pin "8") (pinfunction "O_8") (pintype "open_collector"))
      (node (ref "F") (pin "S2") (pinfunction "P_S2") (pintype "passive"))
      (node (ref "R17") (pin "1") (pinfunction "1_1") (pintype "passive"))
    )
    (net (code "234") (name "~{MQ04-11EQ0}") (class "Default")
      (node (ref "E19") (pin "2") (pinfunction "I0_2") (pintype "input"))
      (node (ref "H") (pin "K1") (pinfunction "P_K1") (pintype "passive"))
    )
    (net (code "235") (name "~{MQ10}") (class "Default")
      (node (ref "F") (pin "A1") (pinfunction "P_A1") (pintype "passive"))
      (node (ref "H") (pin "J1") (pinfunction "P_J1") (pintype "passive"))
    )
    (net (code "236") (name "~{MQ11}") (class "Default")
      (node (ref "F") (pin "B1") (pinfunction "P_B1") (pintype "passive"))
      (node (ref "H") (pin "H1") (pinfunction "P_H1") (pintype "passive"))
    )
    (net (code "237") (name "~{MQ_DATA}") (class "Default")
      (node (ref "F") (pin "B2") (pinfunction "P_B2") (pintype "passive"))
      (node (ref "H") (pin "U2") (pinfunction "P_U2") (pintype "passive"))
    )
    (net (code "238") (name "~{MQ_LOAD}") (class "Default")
      (node (ref "E") (pin "E2") (pinfunction "P_E2") (pintype "passive"))
      (node (ref "E13") (pin "12") (pinfunction "O_12") (pintype "open_collector"))
      (node (ref "F") (pin "R2") (pinfunction "P_R2") (pintype "passive"))
      (node (ref "R2") (pin "1") (pinfunction "1_1") (pintype "passive"))
    )
    (net (code "239") (name "~{MS_DIS}") (class "Default")
      (node (ref "E29") (pin "2") (pinfunction "O_2") (pintype "output"))
      (node (ref "E31") (pin "2") (pinfunction "I1_2") (pintype "input"))
      (node (ref "E36") (pin "13") (pinfunction "I_13") (pintype "input"))
      (node (ref "E44") (pin "12") (pinfunction "I1_12") (pintype "input"))
      (node (ref "E44") (pin "5") (pinfunction "I0_5") (pintype "input"))
      (node (ref "E44") (pin "9") (pinfunction "I1_9") (pintype "input"))
      (node (ref "E49") (pin "12") (pinfunction "I1_12") (pintype "input"))
      (node (ref "E49") (pin "6") (pinfunction "I1_6") (pintype "input"))
      (node (ref "E49") (pin "9") (pinfunction "I1_9") (pintype "input"))
    )
    (net (code "240") (name "~{MS_IR_DIS}") (class "Default")
      (node (ref "E29") (pin "7") (pinfunction "I1_7") (pintype "input"))
      (node (ref "U$2") (pin "CV1") (pinfunction "1_CV1") (pintype "bidirectional"))
    )
    (net (code "241") (name "~{OP1}") (class "Default")
      (node (ref "E21") (pin "8") (pinfunction "O_8") (pintype "output"))
      (node (ref "E25") (pin "12") (pinfunction "I1_12") (pintype "input"))
      (node (ref "E37") (pin "5") (pinfunction "I0_5") (pintype "input"))
      (node (ref "E37") (pin "9") (pinfunction "I1_9") (pintype "input"))
      (node (ref "E42") (pin "13") (pinfunction "I1_13") (pintype "input"))
    )
    (net (code "242") (name "~{OPRF}") (class "Default")
      (node (ref "E20") (pin "2") (pinfunction "O_2") (pintype "output"))
      (node (ref "E7") (pin "5") (pinfunction "I3_5") (pintype "input"))
    )
    (net (code "243") (name "~{OPR_IOT}") (class "Default")
      (node (ref "E16") (pin "6") (pinfunction "O_6") (pintype "output"))
      (node (ref "E22") (pin "9") (pinfunction "I1_9") (pintype "input"))
      (node (ref "E30") (pin "9") (pinfunction "I0_9") (pintype "input"))
      (node (ref "E31") (pin "10") (pinfunction "I1_10") (pintype "input"))
    )
    (net (code "244") (name "~{OPR}") (class "Default")
      (node (ref "E35") (pin "4") (pinfunction "I0_4") (pintype "input"))
      (node (ref "E41") (pin "5") (pinfunction "I0_5") (pintype "input"))
      (node (ref "E46") (pin "13") (pinfunction "0_13") (pintype "output"))
    )
    (net (code "245") (name "~{OVERFLOW}") (class "Default")
      (node (ref "E52") (pin "10") (pinfunction "O_10") (pintype "open_collector"))
      (node (ref "U$2") (pin "BJ2") (pinfunction "1_BJ2") (pintype "bidirectional"))
    )
    (net (code "246") (name "~{PAUSE}") (class "Default")
      (node (ref "E22") (pin "11") (pinfunction "I0_11") (pintype "input"))
      (node (ref "E25") (pin "6") (pinfunction "I1_6") (pintype "input"))
      (node (ref "E9") (pin "11") (pinfunction "I2_11") (pintype "input"))
      (node (ref "U$2") (pin "CD1") (pinfunction "1_CD1") (pintype "bidirectional"))
    )
    (net (code "247") (name "~{PC_LOAD}") (class "Default")
      (node (ref "E15") (pin "4") (pinfunction "O_4") (pintype "open_collector"))
      (node (ref "E53") (pin "1") (pinfunction "O_1") (pintype "open_collector"))
      (node (ref "E53") (pin "10") (pinfunction "O_10") (pintype "open_collector"))
      (node (ref "E53") (pin "4") (pinfunction "O_4") (pintype "open_collector"))
      (node (ref "H") (pin "D1") (pinfunction "P_D1") (pintype "passive"))
      (node (ref "R8") (pin "1") (pinfunction "1_1") (pintype "passive"))
    )
    (net (code "248") (name "~{RIGHT}") (class "Default")
      (node (ref "E23") (pin "4") (pinfunction "O_4") (pintype "open_collector"))
      (node (ref "E24") (pin "9") (pinfunction "C_9") (pintype "input"))
      (node (ref "E28") (pin "12") (pinfunction "O_12") (pintype "open_collector"))
      (node (ref "E28") (pin "4") (pinfunction "O_4") (pintype "open_collector"))
      (node (ref "F") (pin "C1") (pinfunction "P_C1") (pintype "passive"))
      (node (ref "H") (pin "H2") (pinfunction "P_H2") (pintype "passive"))
      (node (ref "R4") (pin "1") (pinfunction "1_1") (pintype "passive"))
    )
    (net (code "249") (name "~{ROM}") (class "Default")
      (node (ref "E11") (pin "9") (pinfunction "I0_9") (pintype "input"))
      (node (ref "U$2") (pin "AU2") (pinfunction "1_AU2") (pintype "bidirectional"))
    )
    (net (code "250") (name "~{SHL_ENA}") (class "Default")
      (node (ref "E") (pin "S2") (pinfunction "P_S2") (pintype "passive"))
      (node (ref "F") (pin "V1") (pinfunction "P_V1") (pintype "passive"))
    )
    (net (code "251") (name "~{SKIP}") (class "Default")
      (node (ref "E22") (pin "8") (pinfunction "I0_8") (pintype "input"))
      (node (ref "U$2") (pin "CS1") (pinfunction "1_CS1") (pintype "bidirectional"))
    )
    (net (code "252") (name "~{TADE}") (class "Default")
      (node (ref "E42") (pin "12") (pinfunction "I0_12") (pintype "input"))
      (node (ref "E42") (pin "8") (pinfunction "O_8") (pintype "output"))
      (node (ref "E7") (pin "1") (pinfunction "I0_1") (pintype "input"))
    )
    (net (code "253") (name "~{TAD}") (class "Default")
      (node (ref "E46") (pin "10") (pinfunction "3_10") (pintype "output"))
      (node (ref "E47") (pin "9") (pinfunction "I_9") (pintype "input"))
      (node (ref "E51") (pin "6") (pinfunction "I1_6") (pintype "input"))
    )
    (net (code "254") (name "~{TS1}") (class "Default")
      (node (ref "E16") (pin "9") (pinfunction "I_9") (pintype "input"))
      (node (ref "U$2") (pin "CK2") (pinfunction "1_CK2") (pintype "bidirectional"))
    )
    (net (code "255") (name "~{TS2}") (class "Default")
      (node (ref "E29") (pin "4") (pinfunction "I0_4") (pintype "input"))
      (node (ref "E34") (pin "11") (pinfunction "I_11") (pintype "input"))
      (node (ref "U$2") (pin "CL2") (pinfunction "1_CL2") (pintype "bidirectional"))
    )
    (net (code "256") (name "~{TS3}") (class "Default")
      (node (ref "E29") (pin "9") (pinfunction "I0_9") (pintype "input"))
      (node (ref "E36") (pin "5") (pinfunction "I_5") (pintype "input"))
      (node (ref "U$2") (pin "CM2") (pinfunction "1_CM2") (pintype "bidirectional"))
    )
    (net (code "257") (name "~{TS4}") (class "Default")
      (node (ref "E34") (pin "9") (pinfunction "I_9") (pintype "input"))
      (node (ref "U$2") (pin "CP2") (pinfunction "1_CP2") (pintype "bidirectional"))
    )
    (net (code "258") (name "~{TWICE}") (class "Default")
      (node (ref "E23") (pin "13") (pinfunction "O_13") (pintype "open_collector"))
      (node (ref "E24") (pin "11") (pinfunction "A_11") (pintype "input"))
      (node (ref "E28") (pin "10") (pinfunction "O_10") (pintype "open_collector"))
      (node (ref "H") (pin "K2") (pinfunction "P_K2") (pintype "passive"))
      (node (ref "R6") (pin "1") (pinfunction "1_1") (pintype "passive"))
    )
  )
)
